# EEZ_CF-DIC_r3B2.net
KiCad netlist of a schematic drawn in EAGLE
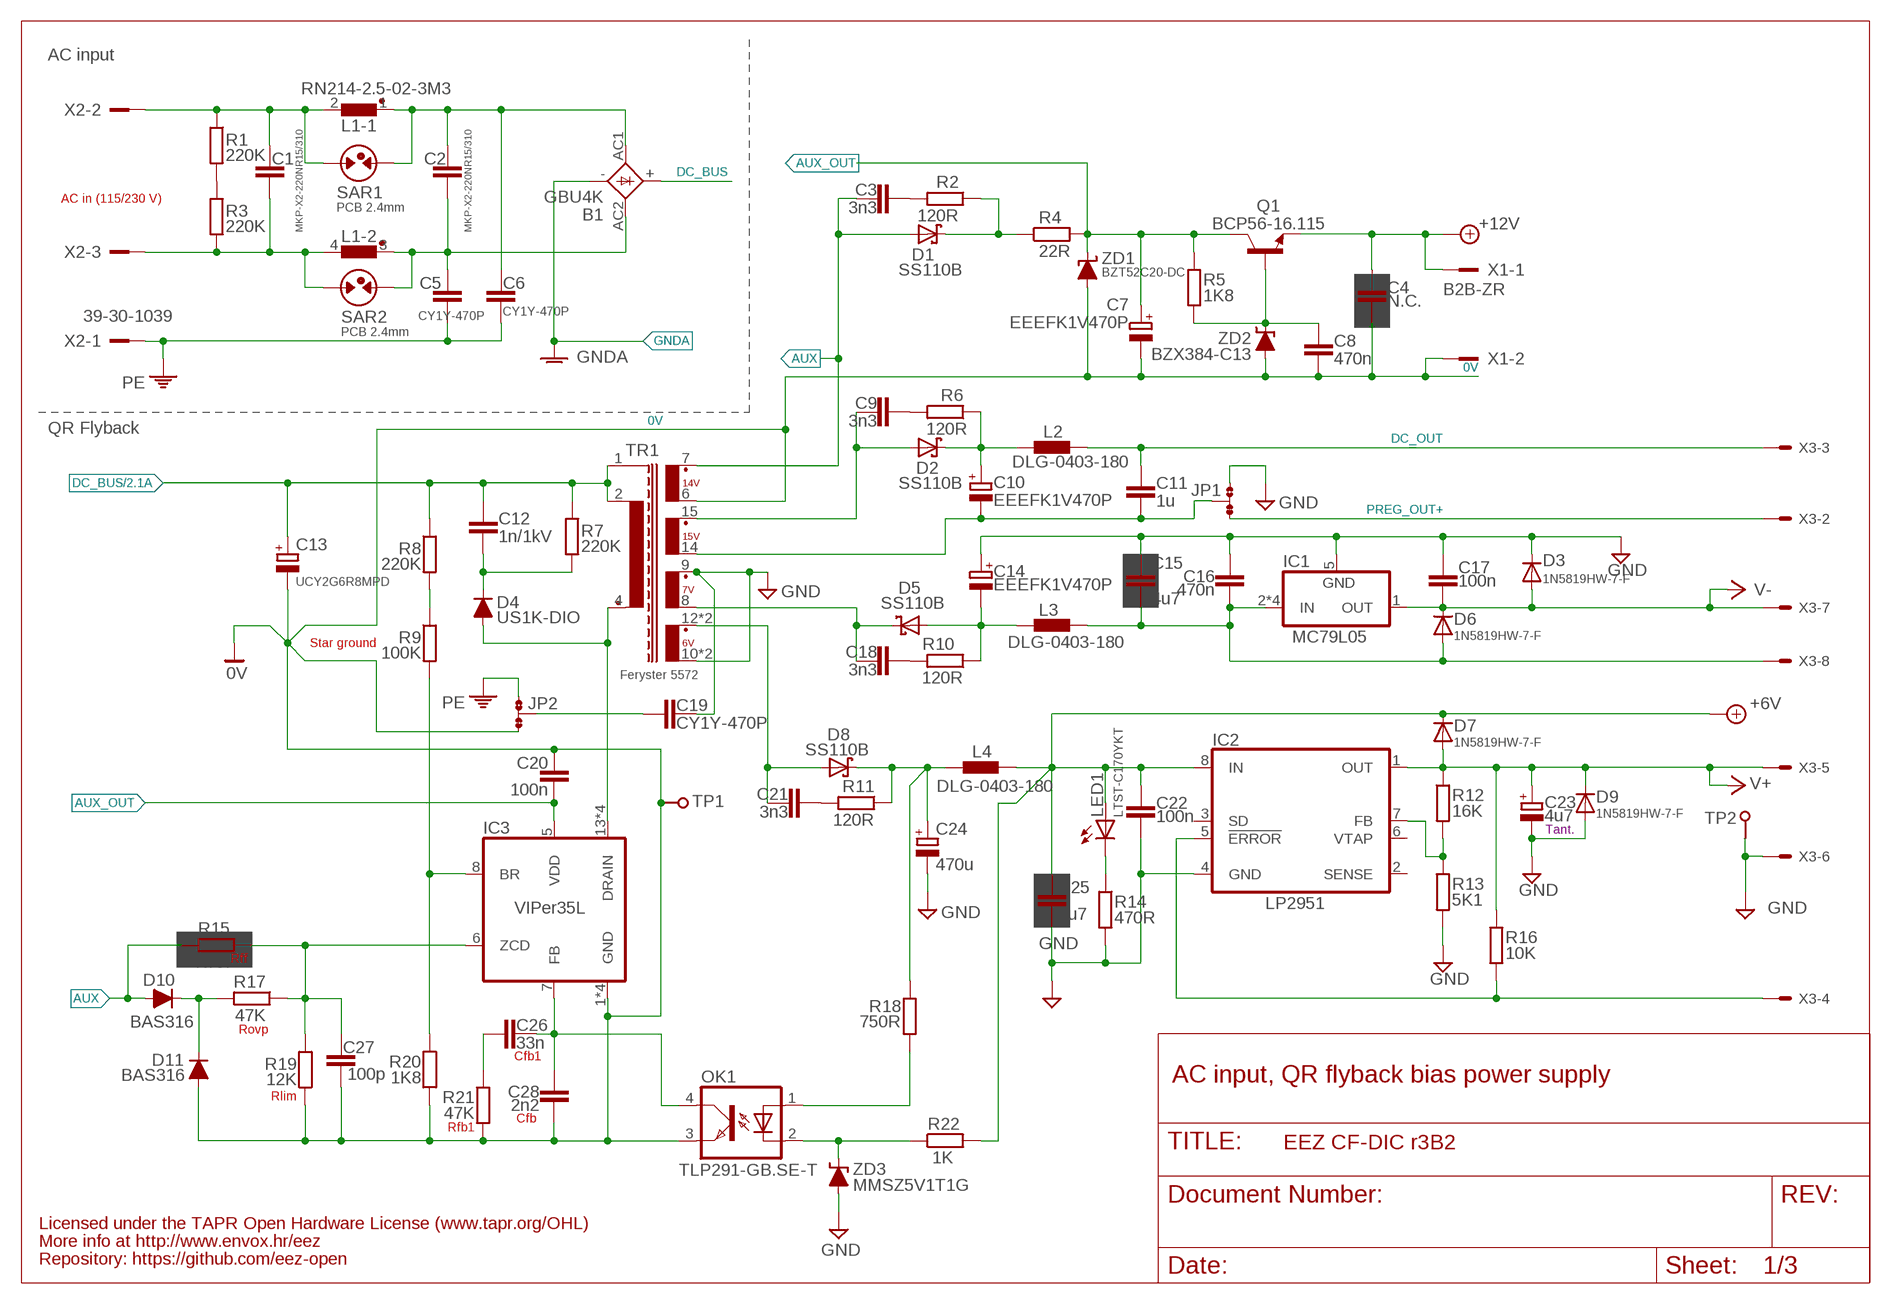
[diagram p0: schematic, sheet 1]
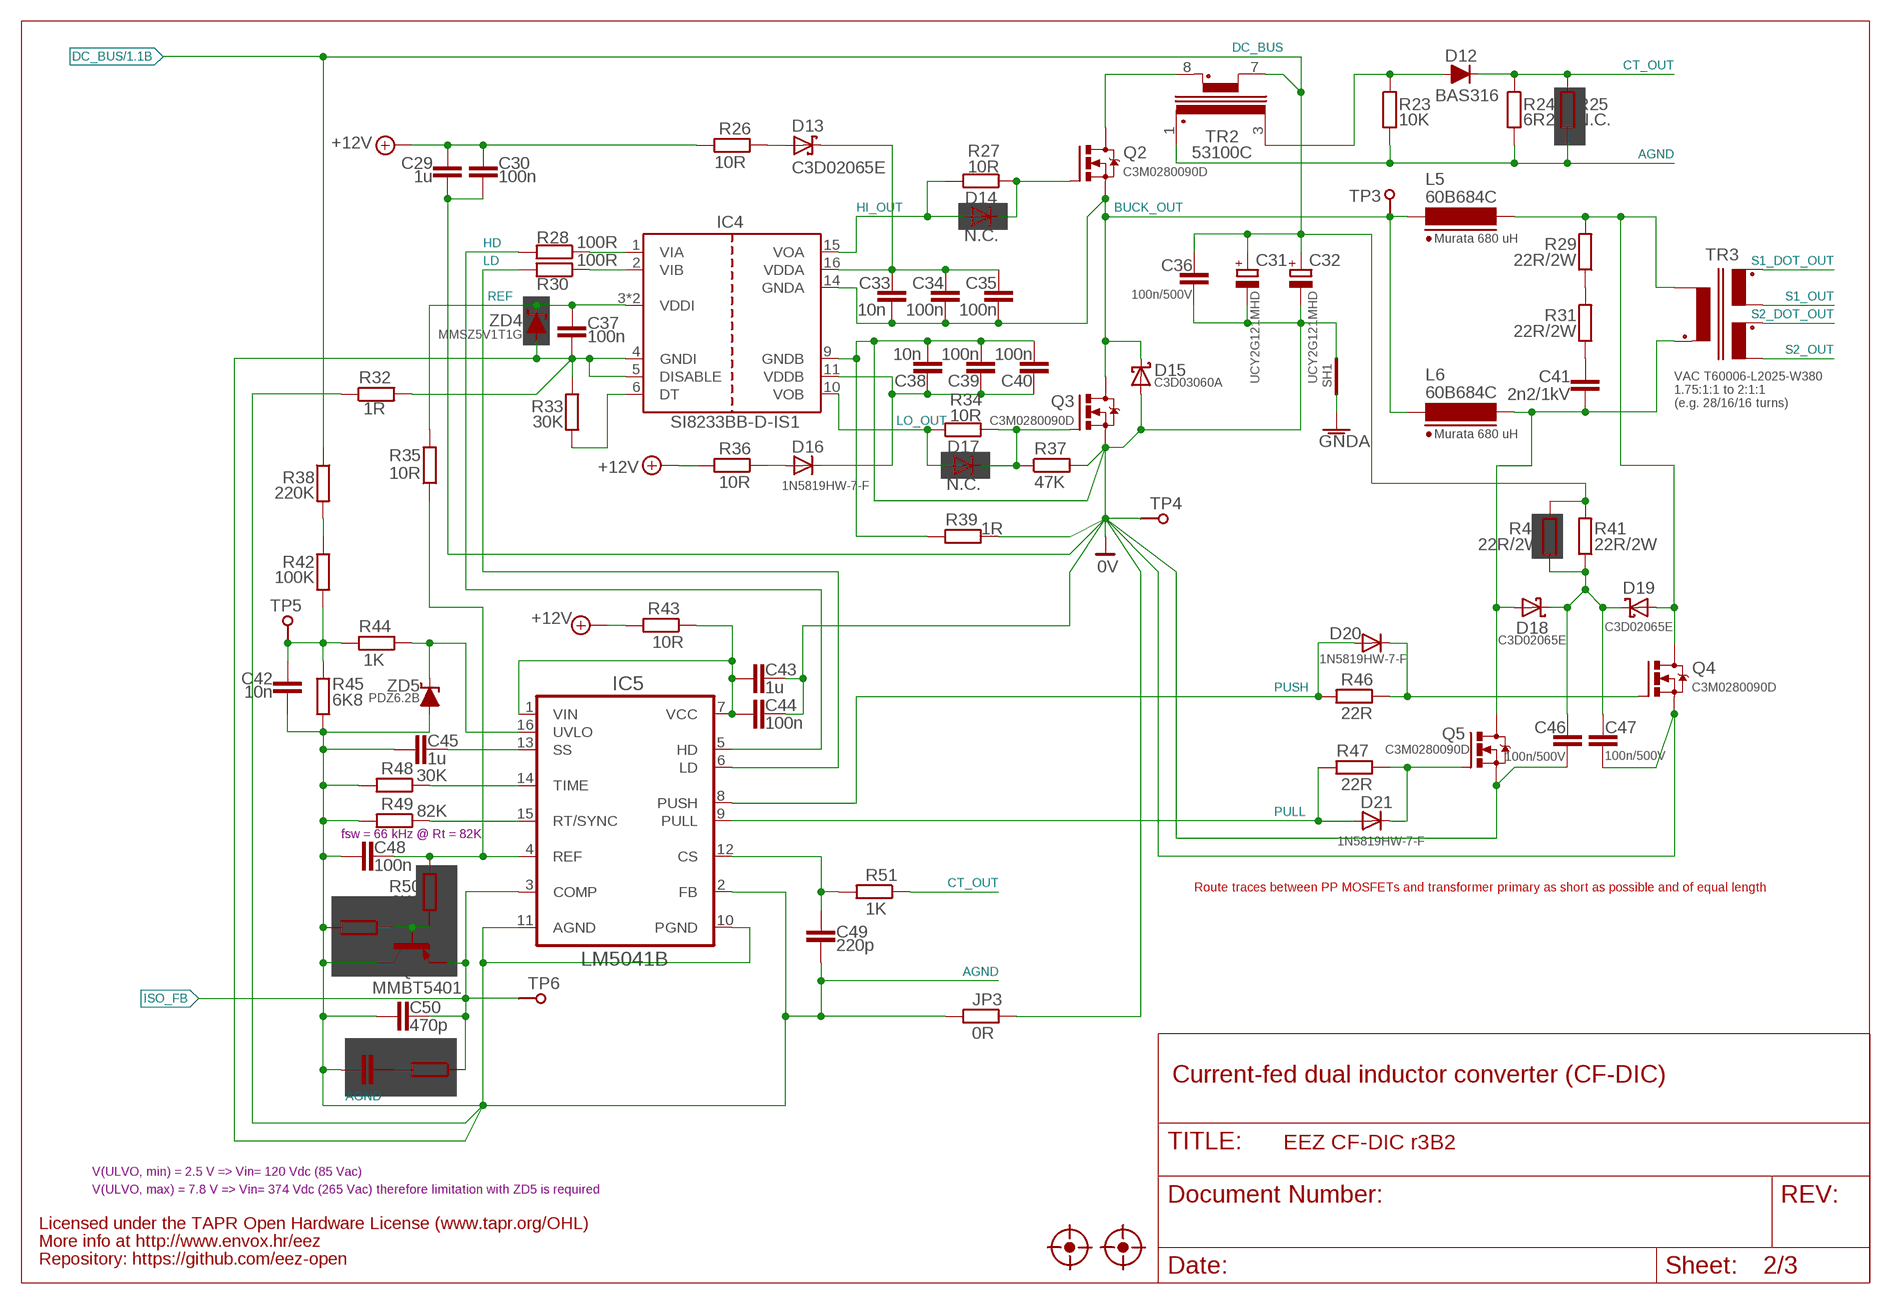
[diagram p1: schematic, sheet 2]
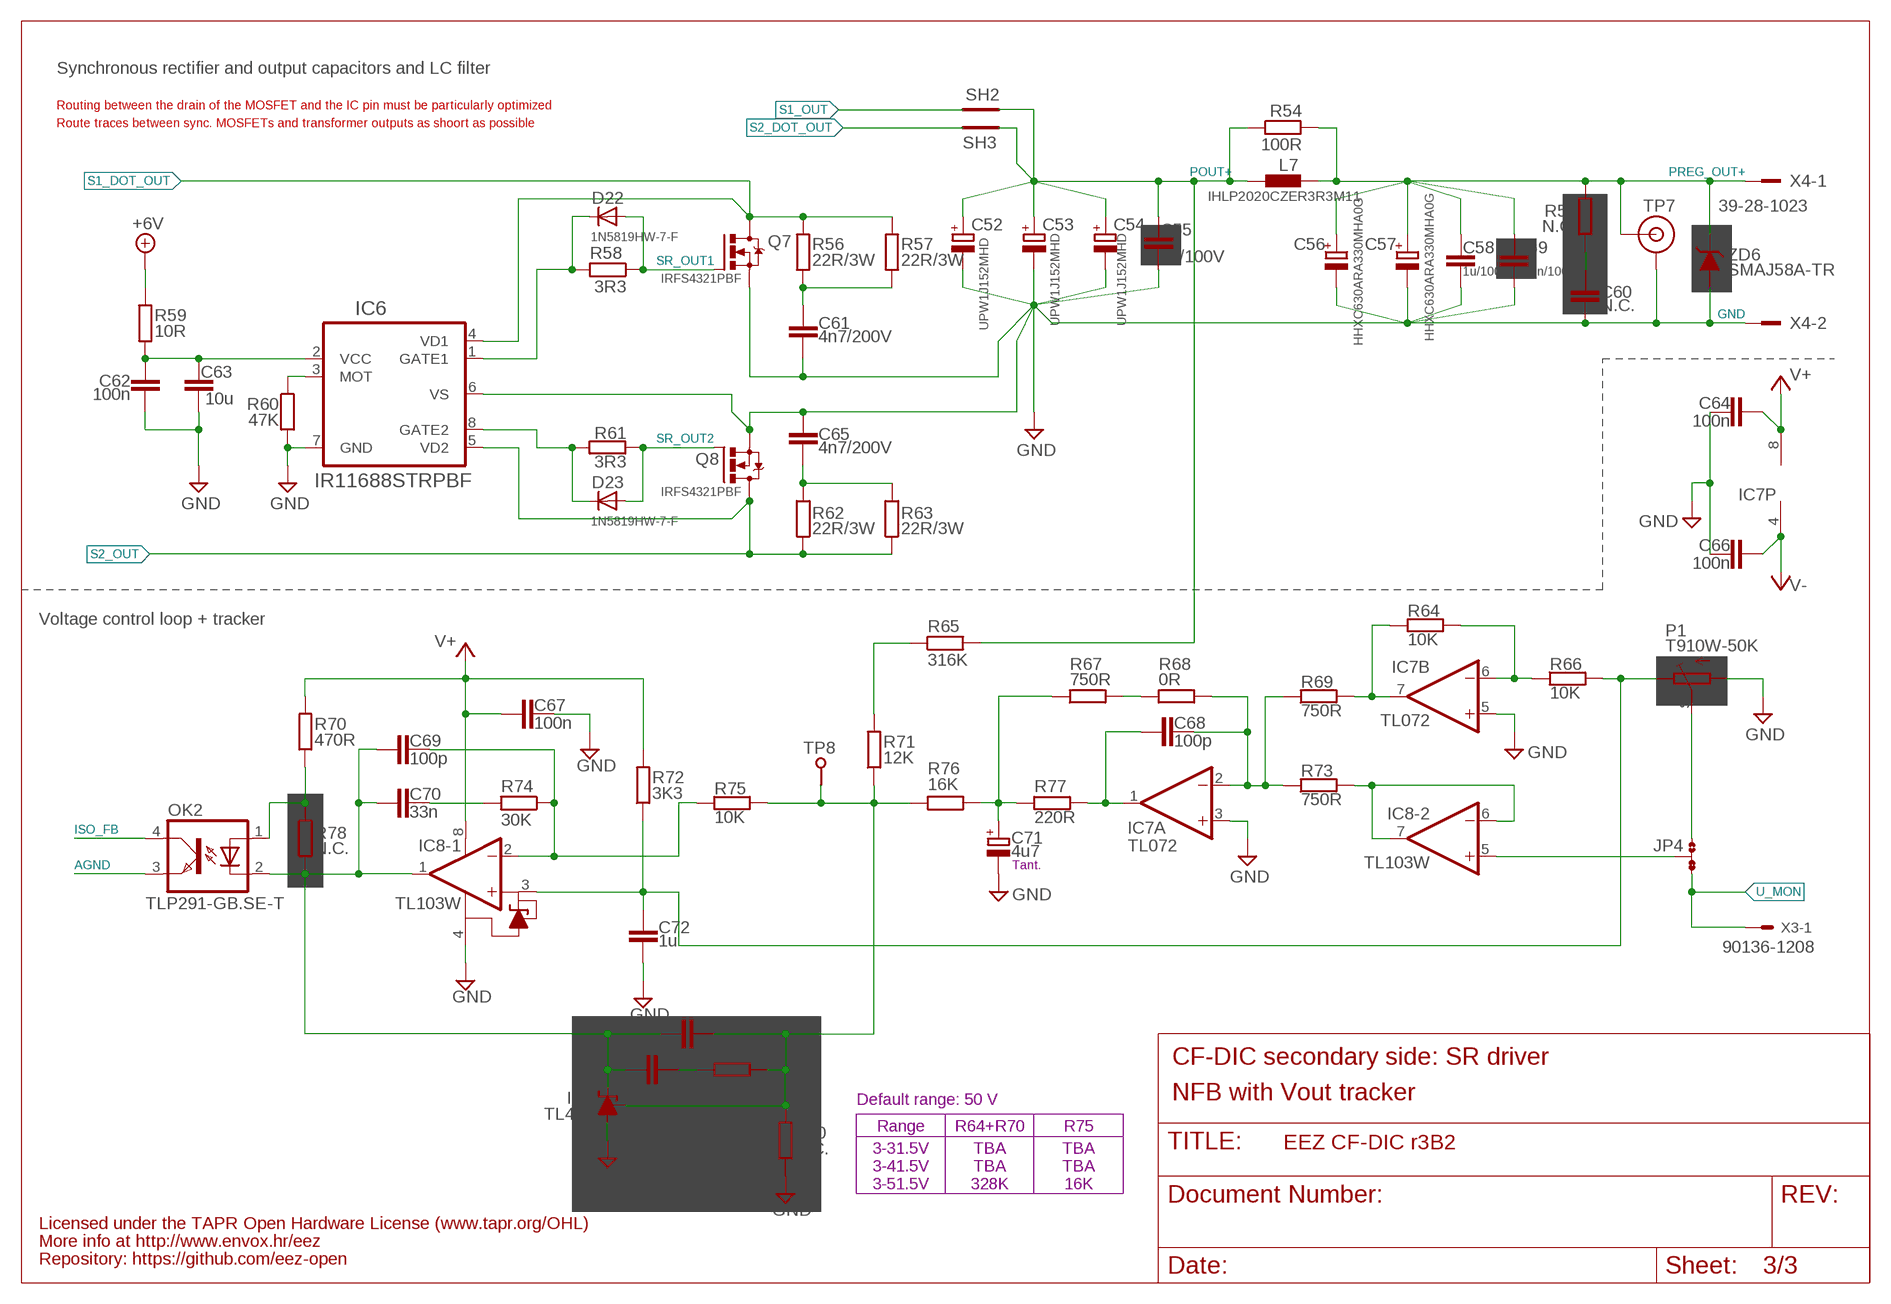
[diagram p2: schematic, sheet 3]

(export (version "E")
  (design (tool "Eeschema 10.0.6"))
  (components
    (comp (ref "C52")
      (value "UPW1J152MHD")
      (footprint "eagle-import:ECAP7.5_18")
      (libsource (lib "eagle-import") (part "ECAP7.5G_18MM"))
    )
    (comp (ref "C53")
      (value "UPW1J152MHD")
      (footprint "eagle-import:ECAP7.5_18")
      (libsource (lib "eagle-import") (part "ECAP7.5G_18MM"))
    )
    (comp (ref "C54")
      (value "UPW1J152MHD")
      (footprint "eagle-import:ECAP7.5_18")
      (libsource (lib "eagle-import") (part "ECAP7.5G_18MM"))
    )
    (comp (ref "C55")
      (value "1u/100V")
      (footprint "eagle-import:C1206")
      (libsource (lib "eagle-import") (part "C-EUC1206"))
    )
    (comp (ref "C56")
      (value "HHXC630ARA330MHA0G ")
      (footprint "eagle-import:CAPAE830X1050N")
      (fields
        (field (name "MPN") "EEE-FK1J470P")
        (field (name "TOLERANCE") "±20 %")
        (field (name "MPN_1") "EEE-FK1J470P")
        (field (name "OC_FARNELL") "9696032  ")
        (field (name "OC_NEWARK") "96K9403")
        (field (name "PACKAGE") "CASE-F")
        (field (name "SUPPLIER") "PANASONIC")
        (field (name "TOLERANCE_1") "±20 %")
        (field (name "VOLTAGERATING") "63 V")
      )
      (libsource (lib "eagle-import") (part "EEE--CASE-FFK1J470P"))
    )
    (comp (ref "C57")
      (value "HHXC630ARA330MHA0G")
      (footprint "eagle-import:CAPAE830X1050N")
      (fields (field (name "MPN") "EEE-FK1J470P") (field (name "TOLERANCE") "±20 %"))
      (libsource (lib "eagle-import") (part "EEE--CASE-FFK1J470P"))
    )
    (comp (ref "C58")
      (value "1u/100V")
      (footprint "eagle-import:C1206")
      (libsource (lib "eagle-import") (part "C-EUC1206"))
    )
    (comp (ref "C59")
      (value "100n/100V")
      (footprint "eagle-import:C0805")
      (libsource (lib "eagle-import") (part "C-EUC0805"))
    )
    (comp (ref "C60")
      (value "N.C.")
      (footprint "eagle-import:C1206")
      (libsource (lib "eagle-import") (part "C-EUC1206"))
    )
    (comp (ref "C61")
      (value "4n7/200V")
      (footprint "eagle-import:C1206")
      (libsource (lib "eagle-import") (part "C-EUC1206"))
    )
    (comp (ref "C62")
      (value "100n")
      (footprint "eagle-import:C0603")
      (libsource (lib "eagle-import") (part "C-EUC0603"))
    )
    (comp (ref "C63")
      (value "10u")
      (footprint "eagle-import:C1210")
      (libsource (lib "eagle-import") (part "C-EUC1210"))
    )
    (comp (ref "C64")
      (value "100n")
      (footprint "eagle-import:C0603")
      (libsource (lib "eagle-import") (part "C-EUC0603"))
    )
    (comp (ref "C65")
      (value "4n7/200V")
      (footprint "eagle-import:C1206")
      (libsource (lib "eagle-import") (part "C-EUC1206"))
    )
    (comp (ref "C66")
      (value "100n")
      (footprint "eagle-import:C0603")
      (libsource (lib "eagle-import") (part "C-EUC0603"))
    )
    (comp (ref "C67")
      (value "100n")
      (footprint "eagle-import:C0603")
      (libsource (lib "eagle-import") (part "C-EUC0603"))
    )
    (comp (ref "C68")
      (value "100p")
      (footprint "eagle-import:C0805")
      (libsource (lib "eagle-import") (part "C-EUC0805"))
    )
    (comp (ref "C69")
      (value "100p")
      (footprint "eagle-import:C0805")
      (libsource (lib "eagle-import") (part "C-EUC0805"))
    )
    (comp (ref "C70")
      (value "33n")
      (footprint "eagle-import:C0805")
      (libsource (lib "eagle-import") (part "C-EUC0805"))
    )
    (comp (ref "C71")
      (value "4u7")
      (footprint "eagle-import:EC1206")
      (libsource (lib "eagle-import") (part "ECAP1206"))
    )
    (comp (ref "C72")
      (value "1u")
      (footprint "eagle-import:C0805")
      (libsource (lib "eagle-import") (part "C-EUC0805"))
    )
    (comp (ref "C73")
      (value "N.C.")
      (footprint "eagle-import:C0805")
      (libsource (lib "eagle-import") (part "C-EUC0805"))
    )
    (comp (ref "C74")
      (value "N.C.")
      (footprint "eagle-import:C0805")
      (libsource (lib "eagle-import") (part "C-EUC0805"))
    )
    (comp (ref "D22")
      (value "1N5819HW-7-F")
      (footprint "eagle-import:SOD323-W")
      (libsource (lib "eagle-import") (part "DIODE-SOD323-W"))
    )
    (comp (ref "D23")
      (value "1N5819HW-7-F")
      (footprint "eagle-import:SOD323-W")
      (libsource (lib "eagle-import") (part "DIODE-SOD323-W"))
    )
    (comp (ref "IC6")
      (value "IR11688STRPBF")
      (footprint "eagle-import:SO8")
      (libsource (lib "eagle-import") (part "IR11688"))
    )
    (comp (ref "IC7")
      (value "TL072")
      (footprint "eagle-import:SOIC127P600X173-8N")
      (libsource (lib "eagle-import") (part "TL072SOIC8"))
    )
    (comp (ref "IC8")
      (value "TL103W")
      (footprint "eagle-import:SOIC127P600X173-8N")
      (libsource (lib "eagle-import") (part "TL103W"))
    )
    (comp (ref "IC9")
      (value "TL431")
      (footprint "eagle-import:SOT103P240X110-3N")
      (libsource (lib "eagle-import") (part "TL431"))
    )
    (comp (ref "JP4")
      (value "JP3-CUT")
      (footprint "eagle-import:JP3-CUT")
      (libsource (lib "eagle-import") (part "JP3-CUT"))
    )
    (comp (ref "L7")
      (value "IHLP2020CZER3R3M11")
      (footprint "eagle-import:IHLP-2020BZ-11")
      (libsource (lib "eagle-import") (part "EEZ_inductors_and_transformers_IHLP-2020BZ-11"))
    )
    (comp (ref "OK2")
      (value "TLP291-GB.SE-T")
      (footprint "eagle-import:SO4")
      (libsource (lib "eagle-import") (part "TLP291"))
    )
    (comp (ref "P1")
      (value "T910W-50K")
      (footprint "eagle-import:S64W")
      (libsource (lib "eagle-import") (part "TRIM_EU-S64W"))
    )
    (comp (ref "Q7")
      (value "IRFS4321PBF")
      (footprint "eagle-import:TO263")
      (libsource (lib "eagle-import") (part "N-MOSFETTO263"))
    )
    (comp (ref "Q8")
      (value "IRFS4321PBF")
      (footprint "eagle-import:TO263")
      (libsource (lib "eagle-import") (part "N-MOSFETTO263"))
    )
    (comp (ref "R54")
      (value "100R")
      (footprint "eagle-import:R0805")
      (libsource (lib "eagle-import") (part "R-EU_R0805"))
    )
    (comp (ref "R55")
      (value "N.C.")
      (footprint "eagle-import:R1210")
      (libsource (lib "eagle-import") (part "R-EU_R1210"))
    )
    (comp (ref "R56")
      (value "22R/3W")
      (footprint "eagle-import:R2512")
      (libsource (lib "eagle-import") (part "R-EU_R2512"))
    )
    (comp (ref "R57")
      (value "22R/3W")
      (footprint "eagle-import:R2512")
      (libsource (lib "eagle-import") (part "R-EU_R2512"))
    )
    (comp (ref "R58")
      (value "3R3")
      (footprint "eagle-import:R0805")
      (libsource (lib "eagle-import") (part "R-EU_R0805"))
    )
    (comp (ref "R59")
      (value "10R")
      (footprint "eagle-import:R0805")
      (libsource (lib "eagle-import") (part "R-EU_R0805"))
    )
    (comp (ref "R60")
      (value "47K")
      (footprint "eagle-import:R0805")
      (libsource (lib "eagle-import") (part "R-EU_R0805"))
    )
    (comp (ref "R61")
      (value "3R3")
      (footprint "eagle-import:R0805")
      (libsource (lib "eagle-import") (part "R-EU_R0805"))
    )
    (comp (ref "R62")
      (value "22R/3W")
      (footprint "eagle-import:R2512")
      (libsource (lib "eagle-import") (part "R-EU_R2512"))
    )
    (comp (ref "R63")
      (value "22R/3W")
      (footprint "eagle-import:R2512")
      (libsource (lib "eagle-import") (part "R-EU_R2512"))
    )
    (comp (ref "R64")
      (value "10K")
      (footprint "eagle-import:R0805")
      (libsource (lib "eagle-import") (part "R-EU_R0805"))
    )
    (comp (ref "R65")
      (value "316K")
      (footprint "eagle-import:R0805")
      (libsource (lib "eagle-import") (part "R-EU_R0805"))
    )
    (comp (ref "R66")
      (value "10K")
      (footprint "eagle-import:R0805")
      (libsource (lib "eagle-import") (part "R-EU_R0805"))
    )
    (comp (ref "R67")
      (value "750R")
      (footprint "eagle-import:R0805")
      (libsource (lib "eagle-import") (part "R-EU_R0805"))
    )
    (comp (ref "R68")
      (value "0R")
      (footprint "eagle-import:R0805")
      (libsource (lib "eagle-import") (part "R-EU_R0805"))
    )
    (comp (ref "R69")
      (value "750R")
      (footprint "eagle-import:R0805")
      (libsource (lib "eagle-import") (part "R-EU_R0805"))
    )
    (comp (ref "R70")
      (value "470R")
      (footprint "eagle-import:R0805")
      (libsource (lib "eagle-import") (part "R-EU_R0805"))
    )
    (comp (ref "R71")
      (value "12K")
      (footprint "eagle-import:R0805")
      (libsource (lib "eagle-import") (part "R-EU_R0805"))
    )
    (comp (ref "R72")
      (value "3K3")
      (footprint "eagle-import:R0805")
      (libsource (lib "eagle-import") (part "R-EU_R0805"))
    )
    (comp (ref "R73")
      (value "750R")
      (footprint "eagle-import:R0805")
      (libsource (lib "eagle-import") (part "R-EU_R0805"))
    )
    (comp (ref "R74")
      (value "30K")
      (footprint "eagle-import:R0805")
      (libsource (lib "eagle-import") (part "R-EU_R0805"))
    )
    (comp (ref "R75")
      (value "10K")
      (footprint "eagle-import:R0805")
      (libsource (lib "eagle-import") (part "R-EU_R0805"))
    )
    (comp (ref "R76")
      (value "16K")
      (footprint "eagle-import:R0805")
      (libsource (lib "eagle-import") (part "R-EU_R0805"))
    )
    (comp (ref "R77")
      (value "220R")
      (footprint "eagle-import:R0805")
      (libsource (lib "eagle-import") (part "R-EU_R0805"))
    )
    (comp (ref "R78")
      (value "N.C.")
      (footprint "eagle-import:R0805")
      (libsource (lib "eagle-import") (part "R-EU_R0805"))
    )
    (comp (ref "R79")
      (value "N.C.")
      (footprint "eagle-import:R0805")
      (libsource (lib "eagle-import") (part "R-EU_R0805"))
    )
    (comp (ref "R80")
      (value "N.C.")
      (footprint "eagle-import:R0805")
      (libsource (lib "eagle-import") (part "R-EU_R0805"))
    )
    (comp (ref "SH2")
      (value "SHORTNOHOLE")
      (footprint "eagle-import:SHORT_NOHOLE")
      (libsource (lib "eagle-import") (part "SHORTNOHOLE"))
    )
    (comp (ref "SH3")
      (value "SHORTNOHOLE")
      (footprint "eagle-import:SHORT_NOHOLE")
      (libsource (lib "eagle-import") (part "SHORTNOHOLE"))
    )
    (comp (ref "TP7")
      (value "TEST_POINT-2")
      (footprint "eagle-import:TP_1.1MM_2")
      (libsource (lib "eagle-import") (part "TEST_POINT-2"))
    )
    (comp (ref "TP8")
      (value "PCB_TEST_TABSHIELD")
      (footprint "eagle-import:PCB_SHIELD_TAB")
      (libsource (lib "eagle-import") (part "PCB_TEST_TABSHIELD"))
    )
    (comp (ref "X3")
      (value "90136-1208")
      (footprint "eagle-import:70543-08")
      (libsource (lib "eagle-import") (part "C-GRID-08-70543"))
    )
    (comp (ref "X4")
      (value "39-28-1023")
      (footprint "eagle-import:MINIFIT_5566-02A")
      (libsource (lib "eagle-import") (part "MINIFIT_5566-02A"))
    )
    (comp (ref "ZD6")
      (value "SMAJ58A-TR")
      (footprint "eagle-import:DO214AC")
      (libsource (lib "eagle-import") (part "PSMAXX"))
    )
    (comp (ref "B1")
      (value "GBU4K")
      (footprint "eagle-import:GBU4K_CRE")
      (libsource (lib "eagle-import") (part "BRIDGE-CREEPAGE"))
    )
    (comp (ref "C1")
      (value "MKP-X2-220NR15/310")
      (footprint "eagle-import:C150-084X183")
      (libsource (lib "eagle-import") (part "C-EU150-084X183"))
    )
    (comp (ref "C2")
      (value "MKP-X2-220NR15/310")
      (footprint "eagle-import:C150-084X183")
      (libsource (lib "eagle-import") (part "C-EU150-084X183"))
    )
    (comp (ref "C3")
      (value "3n3")
      (footprint "eagle-import:C0805")
      (libsource (lib "eagle-import") (part "C-EUC0805"))
    )
    (comp (ref "C4")
      (value "N.C.")
      (footprint "eagle-import:C0603")
      (libsource (lib "eagle-import") (part "C-EUC0603"))
    )
    (comp (ref "C5")
      (value "CY1Y-470P")
      (footprint "eagle-import:CY075-032X103")
      (libsource (lib "eagle-import") (part "C-EUCY"))
    )
    (comp (ref "C6")
      (value "CY1Y-470P")
      (footprint "eagle-import:CY075-032X103")
      (libsource (lib "eagle-import") (part "C-EUCY"))
    )
    (comp (ref "C7")
      (value "EEEFK1V470P")
      (footprint "eagle-import:CAPAE660X610N")
      (libsource (lib "eagle-import") (part "ECAPPANASONIC_H"))
    )
    (comp (ref "C8")
      (value "470n")
      (footprint "eagle-import:C0805")
      (libsource (lib "eagle-import") (part "C-EUC0805"))
    )
    (comp (ref "C9")
      (value "3n3")
      (footprint "eagle-import:C0805")
      (libsource (lib "eagle-import") (part "C-EUC0805"))
    )
    (comp (ref "C10")
      (value "EEEFK1V470P")
      (footprint "eagle-import:CAPAE660X610N")
      (libsource (lib "eagle-import") (part "ECAPPANASONIC_H"))
    )
    (comp (ref "C11")
      (value "1u")
      (footprint "eagle-import:C0805")
      (libsource (lib "eagle-import") (part "C-EUC0805"))
    )
    (comp (ref "C12")
      (value "1n/1kV")
      (footprint "eagle-import:C1210")
      (libsource (lib "eagle-import") (part "C-EUC1210"))
    )
    (comp (ref "C13")
      (value "UCY2G6R8MPD")
      (footprint "eagle-import:ECAP5_10.5")
      (libsource (lib "eagle-import") (part "ECAP5G_10.5MM"))
    )
    (comp (ref "C14")
      (value "EEEFK1V470P")
      (footprint "eagle-import:CAPAE660X610N")
      (libsource (lib "eagle-import") (part "ECAPPANASONIC_H"))
    )
    (comp (ref "C15")
      (value "4u7")
      (footprint "eagle-import:C1206")
      (libsource (lib "eagle-import") (part "C-EUC1206"))
    )
    (comp (ref "C16")
      (value "470n")
      (footprint "eagle-import:C0805")
      (libsource (lib "eagle-import") (part "C-EUC0805"))
    )
    (comp (ref "C17")
      (value "100n")
      (footprint "eagle-import:C0603")
      (libsource (lib "eagle-import") (part "C-EUC0603"))
    )
    (comp (ref "C18")
      (value "3n3")
      (footprint "eagle-import:C0805")
      (libsource (lib "eagle-import") (part "C-EUC0805"))
    )
    (comp (ref "C19")
      (value "CY1Y-470P")
      (footprint "eagle-import:CY075-032X103")
      (libsource (lib "eagle-import") (part "C-EUCY"))
    )
    (comp (ref "C20")
      (value "100n")
      (footprint "eagle-import:C0603")
      (libsource (lib "eagle-import") (part "C-EUC0603"))
    )
    (comp (ref "C21")
      (value "3n3")
      (footprint "eagle-import:C0805")
      (libsource (lib "eagle-import") (part "C-EUC0805"))
    )
    (comp (ref "C22")
      (value "100n")
      (footprint "eagle-import:C0603")
      (libsource (lib "eagle-import") (part "C-EUC0603"))
    )
    (comp (ref "C23")
      (value "4u7")
      (footprint "eagle-import:EC1206")
      (libsource (lib "eagle-import") (part "ECAP1206"))
    )
    (comp (ref "C24")
      (value "470u")
      (footprint "eagle-import:ECAP5_10.5")
      (libsource (lib "eagle-import") (part "ECAP5G_10.5MM"))
    )
    (comp (ref "C25")
      (value "4u7")
      (footprint "eagle-import:C1206")
      (libsource (lib "eagle-import") (part "C-EUC1206"))
    )
    (comp (ref "C26")
      (value "33n")
      (footprint "eagle-import:C0805")
      (libsource (lib "eagle-import") (part "C-EUC0805"))
    )
    (comp (ref "C27")
      (value "100p")
      (footprint "eagle-import:C0805")
      (libsource (lib "eagle-import") (part "C-EUC0805"))
    )
    (comp (ref "C28")
      (value "2n2")
      (footprint "eagle-import:C0805")
      (libsource (lib "eagle-import") (part "C-EUC0805"))
    )
    (comp (ref "D1")
      (value "SS110B")
      (footprint "eagle-import:SMB")
      (libsource (lib "eagle-import") (part "SCHOTTKYSMB"))
    )
    (comp (ref "D2")
      (value "SS110B")
      (footprint "eagle-import:SMB")
      (libsource (lib "eagle-import") (part "SCHOTTKYSMB"))
    )
    (comp (ref "D3")
      (value "1N5819HW-7-F")
      (footprint "eagle-import:SOD323-W")
      (libsource (lib "eagle-import") (part "DIODE-SOD323-W"))
    )
    (comp (ref "D4")
      (value "US1K-DIO")
      (footprint "eagle-import:DO214AA")
      (libsource (lib "eagle-import") (part "DIODEDO214AA"))
    )
    (comp (ref "D5")
      (value "SS110B")
      (footprint "eagle-import:SMB")
      (libsource (lib "eagle-import") (part "SCHOTTKYSMB"))
    )
    (comp (ref "D6")
      (value "1N5819HW-7-F")
      (footprint "eagle-import:SOD323-W")
      (libsource (lib "eagle-import") (part "DIODE-SOD323-W"))
    )
    (comp (ref "D7")
      (value "1N5819HW-7-F")
      (footprint "eagle-import:SOD323-W")
      (libsource (lib "eagle-import") (part "DIODE-SOD323-W"))
    )
    (comp (ref "D8")
      (value "SS110B")
      (footprint "eagle-import:SMB")
      (libsource (lib "eagle-import") (part "SCHOTTKYSMB"))
    )
    (comp (ref "D9")
      (value "1N5819HW-7-F")
      (footprint "eagle-import:SOD323-W")
      (libsource (lib "eagle-import") (part "DIODE-SOD323-W"))
    )
    (comp (ref "D10")
      (value "BAS316")
      (footprint "eagle-import:SOD323-R")
      (libsource (lib "eagle-import") (part "DIODESOD323R"))
    )
    (comp (ref "D11")
      (value "BAS316")
      (footprint "eagle-import:SOD323-R")
      (libsource (lib "eagle-import") (part "DIODESOD323R"))
    )
    (comp (ref "IC1")
      (value "MC79L05")
      (footprint "eagle-import:SOIC127P600X173-8N")
      (libsource (lib "eagle-import") (part "MC79LXXSOIC"))
    )
    (comp (ref "IC2")
      (value "LP2951")
      (footprint "eagle-import:SOIC127P600X175-8N")
      (libsource (lib "eagle-import") (part "LP2951SO8"))
    )
    (comp (ref "IC3")
      (value "VIPer35L")
      (footprint "eagle-import:SOIC-16")
      (libsource (lib "eagle-import") (part "VIPER35"))
    )
    (comp (ref "JP1")
      (value "JP3-CUT")
      (footprint "eagle-import:JP3-CUT")
      (libsource (lib "eagle-import") (part "JP3-CUT"))
    )
    (comp (ref "JP2")
      (value "JP3-CUT")
      (footprint "eagle-import:JP3-CUT")
      (libsource (lib "eagle-import") (part "JP3-CUT"))
    )
    (comp (ref "L1")
      (value "RN214-2.5-02-3M3")
      (footprint "eagle-import:RN214")
      (fields (field (name "FARNELL") "1191518"))
      (libsource (lib "eagle-import") (part "EEZ_inductors_and_transformers_RN214"))
    )
    (comp (ref "L2")
      (value "DLG-0403-180")
      (footprint "eagle-import:DE0403")
      (libsource (lib "eagle-import") (part "EEZ_inductors_and_transformers_DE0403"))
    )
    (comp (ref "L3")
      (value "DLG-0403-180")
      (footprint "eagle-import:DE0403")
      (libsource (lib "eagle-import") (part "EEZ_inductors_and_transformers_DE0403"))
    )
    (comp (ref "L4")
      (value "DLG-0403-180")
      (footprint "eagle-import:DE0403")
      (libsource (lib "eagle-import") (part "EEZ_inductors_and_transformers_DE0403"))
    )
    (comp (ref "LED1")
      (value "LTST-C170YKT")
      (footprint "eagle-import:LED_0805")
      (libsource (lib "eagle-import") (part "LED0805"))
    )
    (comp (ref "OK1")
      (value "TLP291-GB.SE-T")
      (footprint "eagle-import:SO4")
      (libsource (lib "eagle-import") (part "TLP291"))
    )
    (comp (ref "Q1")
      (value "BCP56-16.115")
      (footprint "eagle-import:SOT230P700X180-4N")
      (libsource (lib "eagle-import") (part "BCP56"))
    )
    (comp (ref "R1")
      (value "220K")
      (footprint "eagle-import:R1206")
      (libsource (lib "eagle-import") (part "R-EU_R1206"))
    )
    (comp (ref "R2")
      (value "120R")
      (footprint "eagle-import:R0805")
      (libsource (lib "eagle-import") (part "R-EU_R0805"))
    )
    (comp (ref "R3")
      (value "220K")
      (footprint "eagle-import:R1206")
      (libsource (lib "eagle-import") (part "R-EU_R1206"))
    )
    (comp (ref "R4")
      (value "22R")
      (footprint "eagle-import:R0805")
      (libsource (lib "eagle-import") (part "R-EU_R0805"))
    )
    (comp (ref "R5")
      (value "1K8")
      (footprint "eagle-import:R0805")
      (libsource (lib "eagle-import") (part "R-EU_R0805"))
    )
    (comp (ref "R6")
      (value "120R")
      (footprint "eagle-import:R0805")
      (libsource (lib "eagle-import") (part "R-EU_R0805"))
    )
    (comp (ref "R7")
      (value "220K")
      (footprint "eagle-import:R1206")
      (libsource (lib "eagle-import") (part "R-EU_R1206"))
    )
    (comp (ref "R8")
      (value "220K")
      (footprint "eagle-import:R1206")
      (libsource (lib "eagle-import") (part "R-EU_R1206"))
    )
    (comp (ref "R9")
      (value "100K")
      (footprint "eagle-import:R0805")
      (libsource (lib "eagle-import") (part "R-EU_R0805"))
    )
    (comp (ref "R10")
      (value "120R")
      (footprint "eagle-import:R0805")
      (libsource (lib "eagle-import") (part "R-EU_R0805"))
    )
    (comp (ref "R11")
      (value "120R")
      (footprint "eagle-import:R0805")
      (libsource (lib "eagle-import") (part "R-EU_R0805"))
    )
    (comp (ref "R12")
      (value "16K")
      (footprint "eagle-import:R0805")
      (libsource (lib "eagle-import") (part "R-EU_R0805"))
    )
    (comp (ref "R13")
      (value "5K1")
      (footprint "eagle-import:R0805")
      (libsource (lib "eagle-import") (part "R-EU_R0805"))
    )
    (comp (ref "R14")
      (value "470R")
      (footprint "eagle-import:R0805")
      (libsource (lib "eagle-import") (part "R-EU_R0805"))
    )
    (comp (ref "R15")
      (value "N.C.")
      (footprint "eagle-import:R0805")
      (libsource (lib "eagle-import") (part "R-EU_R0805"))
    )
    (comp (ref "R16")
      (value "10K")
      (footprint "eagle-import:R0805")
      (libsource (lib "eagle-import") (part "R-EU_R0805"))
    )
    (comp (ref "R17")
      (value "47K")
      (footprint "eagle-import:R0805")
      (libsource (lib "eagle-import") (part "R-EU_R0805"))
    )
    (comp (ref "R18")
      (value "750R")
      (footprint "eagle-import:R0805")
      (libsource (lib "eagle-import") (part "R-EU_R0805"))
    )
    (comp (ref "R19")
      (value "12K")
      (footprint "eagle-import:R0805")
      (libsource (lib "eagle-import") (part "R-EU_R0805"))
    )
    (comp (ref "R20")
      (value "1K8")
      (footprint "eagle-import:R0805")
      (libsource (lib "eagle-import") (part "R-EU_R0805"))
    )
    (comp (ref "R21")
      (value "47K")
      (footprint "eagle-import:R0805")
      (libsource (lib "eagle-import") (part "R-EU_R0805"))
    )
    (comp (ref "R22")
      (value "1K")
      (footprint "eagle-import:R0805")
      (libsource (lib "eagle-import") (part "R-EU_R0805"))
    )
    (comp (ref "SAR1")
      (value "PCB 2.4mm")
      (footprint "eagle-import:PCB-SAR_2.4MM")
      (libsource (lib "eagle-import") (part "SARPCB-2.4MM"))
    )
    (comp (ref "SAR2")
      (value "PCB 2.4mm")
      (footprint "eagle-import:PCB-SAR_2.4MM")
      (libsource (lib "eagle-import") (part "SARPCB-2.4MM"))
    )
    (comp (ref "TP1")
      (value "PCB_TEST_TABSHIELD")
      (footprint "eagle-import:PCB_SHIELD_TAB")
      (libsource (lib "eagle-import") (part "PCB_TEST_TABSHIELD"))
    )
    (comp (ref "TP2")
      (value "PCB_TEST_TABSHIELD")
      (footprint "eagle-import:PCB_SHIELD_TAB")
      (libsource (lib "eagle-import") (part "PCB_TEST_TABSHIELD"))
    )
    (comp (ref "TR1")
      (value "Feryster 5572")
      (footprint "eagle-import:FERYSTER_5572")
      (libsource (lib "eagle-import") (part "EEZ_inductors_and_transformers_FERYSTER_5572"))
    )
    (comp (ref "X1")
      (value "B2B-ZR")
      (footprint "eagle-import:B2B-ZR")
      (libsource (lib "eagle-import") (part "B2B-ZR"))
    )
    (comp (ref "X2")
      (value "39-30-1039")
      (footprint "eagle-import:MINIFIT_39301039_CRE")
      (libsource (lib "eagle-import") (part "MINIFIT_39301039-CREEPAGE"))
    )
    (comp (ref "ZD1")
      (value "BZT52C20-DC")
      (footprint "eagle-import:SOD123FL")
      (libsource (lib "eagle-import") (part "ZENER-DIODESOD123FL"))
    )
    (comp (ref "ZD2")
      (value "BZX384-C13")
      (footprint "eagle-import:SOD323-W")
      (libsource (lib "eagle-import") (part "ZENER-DIODESOD323"))
    )
    (comp (ref "ZD3")
      (value "MMSZ5V1T1G")
      (footprint "eagle-import:SOD323-W")
      (libsource (lib "eagle-import") (part "ZENER-DIODESOD323"))
    )
    (comp (ref "C29")
      (value "1u")
      (footprint "eagle-import:C0805")
      (libsource (lib "eagle-import") (part "C-EUC0805"))
    )
    (comp (ref "C30")
      (value "100n")
      (footprint "eagle-import:C0603")
      (libsource (lib "eagle-import") (part "C-EUC0603"))
    )
    (comp (ref "C31")
      (value "UCY2G121MHD")
      (footprint "eagle-import:ECAP7.5_18")
      (libsource (lib "eagle-import") (part "ECAP7.5G_18MM"))
    )
    (comp (ref "C32")
      (value "UCY2G121MHD")
      (footprint "eagle-import:ECAP7.5_18")
      (libsource (lib "eagle-import") (part "ECAP7.5G_18MM"))
    )
    (comp (ref "C33")
      (value "10n")
      (footprint "eagle-import:C0603")
      (libsource (lib "eagle-import") (part "C-EUC0603"))
    )
    (comp (ref "C34")
      (value "100n")
      (footprint "eagle-import:C0603")
      (libsource (lib "eagle-import") (part "C-EUC0603"))
    )
    (comp (ref "C35")
      (value "100n")
      (footprint "eagle-import:C0603")
      (libsource (lib "eagle-import") (part "C-EUC0603"))
    )
    (comp (ref "C36")
      (value "100n/500V")
      (footprint "eagle-import:C1812")
      (libsource (lib "eagle-import") (part "C-EUC1812"))
    )
    (comp (ref "C37")
      (value "100n")
      (footprint "eagle-import:C0603")
      (libsource (lib "eagle-import") (part "C-EUC0603"))
    )
    (comp (ref "C38")
      (value "10n")
      (footprint "eagle-import:C0603")
      (libsource (lib "eagle-import") (part "C-EUC0603"))
    )
    (comp (ref "C39")
      (value "100n")
      (footprint "eagle-import:C0603")
      (libsource (lib "eagle-import") (part "C-EUC0603"))
    )
    (comp (ref "C40")
      (value "100n")
      (footprint "eagle-import:C0603")
      (libsource (lib "eagle-import") (part "C-EUC0603"))
    )
    (comp (ref "C41")
      (value "2n2/1kV")
      (footprint "eagle-import:C1210")
      (libsource (lib "eagle-import") (part "C-EUC1210"))
    )
    (comp (ref "C42")
      (value "10n")
      (footprint "eagle-import:C0603")
      (libsource (lib "eagle-import") (part "C-EUC0603"))
    )
    (comp (ref "C43")
      (value "1u")
      (footprint "eagle-import:C0805")
      (libsource (lib "eagle-import") (part "C-EUC0805"))
    )
    (comp (ref "C44")
      (value "100n")
      (footprint "eagle-import:C0603")
      (libsource (lib "eagle-import") (part "C-EUC0603"))
    )
    (comp (ref "C45")
      (value "1u")
      (footprint "eagle-import:C0805")
      (libsource (lib "eagle-import") (part "C-EUC0805"))
    )
    (comp (ref "C46")
      (value "100n/500V")
      (footprint "eagle-import:C1812")
      (libsource (lib "eagle-import") (part "C-EUC1812"))
    )
    (comp (ref "C47")
      (value "100n/500V")
      (footprint "eagle-import:C1812")
      (libsource (lib "eagle-import") (part "C-EUC1812"))
    )
    (comp (ref "C48")
      (value "100n")
      (footprint "eagle-import:C0603")
      (libsource (lib "eagle-import") (part "C-EUC0603"))
    )
    (comp (ref "C49")
      (value "220p")
      (footprint "eagle-import:C0805")
      (libsource (lib "eagle-import") (part "C-EUC0805"))
    )
    (comp (ref "C50")
      (value "470p")
      (footprint "eagle-import:C0805")
      (libsource (lib "eagle-import") (part "C-EUC0805"))
    )
    (comp (ref "C51")
      (value "N.C.")
      (footprint "eagle-import:C0805")
      (libsource (lib "eagle-import") (part "C-EUC0805"))
    )
    (comp (ref "D12")
      (value "BAS316")
      (footprint "eagle-import:SOD323-R")
      (libsource (lib "eagle-import") (part "DIODESOD323R"))
    )
    (comp (ref "D13")
      (value "C3D02065E")
      (footprint "eagle-import:TO252")
      (libsource (lib "eagle-import") (part "SCHOTTKY-2"))
    )
    (comp (ref "D14")
      (value "N.C.")
      (footprint "eagle-import:SOD323-W")
      (libsource (lib "eagle-import") (part "DIODE-SOD323-W"))
    )
    (comp (ref "D15")
      (value "C3D03060A")
      (footprint "eagle-import:TO220-2")
      (libsource (lib "eagle-import") (part "SCHOTTKY-TO220"))
    )
    (comp (ref "D16")
      (value "1N5819HW-7-F")
      (footprint "eagle-import:SOD323-W")
      (libsource (lib "eagle-import") (part "DIODE-SOD323-W"))
    )
    (comp (ref "D17")
      (value "N.C.")
      (footprint "eagle-import:SOD323-W")
      (libsource (lib "eagle-import") (part "DIODE-SOD323-W"))
    )
    (comp (ref "D18")
      (value "C3D02065E")
      (footprint "eagle-import:TO252")
      (libsource (lib "eagle-import") (part "SCHOTTKY-2"))
    )
    (comp (ref "D19")
      (value "C3D02065E")
      (footprint "eagle-import:TO252")
      (libsource (lib "eagle-import") (part "SCHOTTKY-2"))
    )
    (comp (ref "D20")
      (value "1N5819HW-7-F")
      (footprint "eagle-import:SOD323-W")
      (libsource (lib "eagle-import") (part "DIODE-SOD323-W"))
    )
    (comp (ref "D21")
      (value "1N5819HW-7-F")
      (footprint "eagle-import:SOD323-W")
      (libsource (lib "eagle-import") (part "DIODE-SOD323-W"))
    )
    (comp (ref "FM1")
      (value "FIDUCIAL_2")
      (footprint "eagle-import:FIDUCIAL_DUAL")
      (libsource (lib "eagle-import") (part "FIDUCIAL_2"))
    )
    (comp (ref "FM2")
      (value "FIDUCIAL_2")
      (footprint "eagle-import:FIDUCIAL_DUAL")
      (libsource (lib "eagle-import") (part "FIDUCIAL_2"))
    )
    (comp (ref "IC4")
      (value "SI8233BB-D-IS1")
      (footprint "eagle-import:SOIC-16")
      (libsource (lib "eagle-import") (part "SI8233"))
    )
    (comp (ref "IC5")
      (value "LM5041B")
      (footprint "eagle-import:MTC16")
      (fields (field (name "MANUFACTURER_PART_NUMBER") "lm5041mtcnopb"))
      (libsource (lib "eagle-import") (part "LM5041"))
    )
    (comp (ref "JP3")
      (value "0R")
      (footprint "eagle-import:R0805")
      (libsource (lib "eagle-import") (part "R-EU_R0805"))
    )
    (comp (ref "L5")
      (value "60B684C")
      (footprint "eagle-import:MURATA_6000B")
      (libsource (lib "eagle-import") (part "EEZ_inductors_and_transformers_MURATA_6000B"))
    )
    (comp (ref "L6")
      (value "60B684C")
      (footprint "eagle-import:MURATA_6000B")
      (libsource (lib "eagle-import") (part "EEZ_inductors_and_transformers_MURATA_6000B"))
    )
    (comp (ref "Q2")
      (value "C3M0280090D")
      (footprint "eagle-import:TO247BV")
      (libsource (lib "eagle-import") (part "IRFP240"))
    )
    (comp (ref "Q3")
      (value "C3M0280090D")
      (footprint "eagle-import:TO247BV")
      (libsource (lib "eagle-import") (part "IRFP240"))
    )
    (comp (ref "Q4")
      (value "C3M0280090D")
      (footprint "eagle-import:TO247BV")
      (libsource (lib "eagle-import") (part "IRFP240"))
    )
    (comp (ref "Q5")
      (value "C3M0280090D")
      (footprint "eagle-import:TO247BV")
      (libsource (lib "eagle-import") (part "IRFP240"))
    )
    (comp (ref "Q6")
      (value "MMBT5401")
      (footprint "eagle-import:SOT23-BEC")
      (libsource (lib "eagle-import") (part "-PNP-SOT23-BECBC857B"))
    )
    (comp (ref "R23")
      (value "10K")
      (footprint "eagle-import:R0805")
      (libsource (lib "eagle-import") (part "R-EU_R0805"))
    )
    (comp (ref "R24")
      (value "6R2")
      (footprint "eagle-import:R0805")
      (libsource (lib "eagle-import") (part "R-EU_R0805"))
    )
    (comp (ref "R25")
      (value "N.C.")
      (footprint "eagle-import:R0805")
      (libsource (lib "eagle-import") (part "R-EU_R0805"))
    )
    (comp (ref "R26")
      (value "10R")
      (footprint "eagle-import:R0805")
      (libsource (lib "eagle-import") (part "R-EU_R0805"))
    )
    (comp (ref "R27")
      (value "10R")
      (footprint "eagle-import:R0805")
      (libsource (lib "eagle-import") (part "R-EU_R0805"))
    )
    (comp (ref "R28")
      (value "100R")
      (footprint "eagle-import:R0805")
      (libsource (lib "eagle-import") (part "R-EU_R0805"))
    )
    (comp (ref "R29")
      (value "22R/2W")
      (footprint "eagle-import:R2512")
      (libsource (lib "eagle-import") (part "R-EU_R2512"))
    )
    (comp (ref "R30")
      (value "100R")
      (footprint "eagle-import:R0805")
      (libsource (lib "eagle-import") (part "R-EU_R0805"))
    )
    (comp (ref "R31")
      (value "22R/2W")
      (footprint "eagle-import:R2512")
      (libsource (lib "eagle-import") (part "R-EU_R2512"))
    )
    (comp (ref "R32")
      (value "1R")
      (footprint "eagle-import:R0805")
      (libsource (lib "eagle-import") (part "R-EU_R0805"))
    )
    (comp (ref "R33")
      (value "30K")
      (footprint "eagle-import:R0805")
      (libsource (lib "eagle-import") (part "R-EU_R0805"))
    )
    (comp (ref "R34")
      (value "10R")
      (footprint "eagle-import:R0805")
      (libsource (lib "eagle-import") (part "R-EU_R0805"))
    )
    (comp (ref "R35")
      (value "10R")
      (footprint "eagle-import:R0805")
      (libsource (lib "eagle-import") (part "R-EU_R0805"))
    )
    (comp (ref "R36")
      (value "10R")
      (footprint "eagle-import:R0805")
      (libsource (lib "eagle-import") (part "R-EU_R0805"))
    )
    (comp (ref "R37")
      (value "47K")
      (footprint "eagle-import:R0805")
      (libsource (lib "eagle-import") (part "R-EU_R0805"))
    )
    (comp (ref "R38")
      (value "220K")
      (footprint "eagle-import:R1206")
      (libsource (lib "eagle-import") (part "R-EU_R1206"))
    )
    (comp (ref "R39")
      (value "1R")
      (footprint "eagle-import:R0805")
      (libsource (lib "eagle-import") (part "R-EU_R0805"))
    )
    (comp (ref "R40")
      (value "22R/2W")
      (footprint "eagle-import:R2512")
      (libsource (lib "eagle-import") (part "R-EU_R2512"))
    )
    (comp (ref "R41")
      (value "22R/2W")
      (footprint "eagle-import:R2512")
      (libsource (lib "eagle-import") (part "R-EU_R2512"))
    )
    (comp (ref "R42")
      (value "100K")
      (footprint "eagle-import:R0805")
      (libsource (lib "eagle-import") (part "R-EU_R0805"))
    )
    (comp (ref "R43")
      (value "10R")
      (footprint "eagle-import:R0805")
      (libsource (lib "eagle-import") (part "R-EU_R0805"))
    )
    (comp (ref "R44")
      (value "1K")
      (footprint "eagle-import:R0805")
      (libsource (lib "eagle-import") (part "R-EU_R0805"))
    )
    (comp (ref "R45")
      (value "6K8")
      (footprint "eagle-import:R0805")
      (libsource (lib "eagle-import") (part "R-EU_R0805"))
    )
    (comp (ref "R46")
      (value "22R")
      (footprint "eagle-import:R0805")
      (libsource (lib "eagle-import") (part "R-EU_R0805"))
    )
    (comp (ref "R47")
      (value "22R")
      (footprint "eagle-import:R0805")
      (libsource (lib "eagle-import") (part "R-EU_R0805"))
    )
    (comp (ref "R48")
      (value "30K")
      (footprint "eagle-import:R0805")
      (libsource (lib "eagle-import") (part "R-EU_R0805"))
    )
    (comp (ref "R49")
      (value "82K")
      (footprint "eagle-import:R0805")
      (libsource (lib "eagle-import") (part "R-EU_R0805"))
    )
    (comp (ref "R50")
      (value "6K8")
      (footprint "eagle-import:R0805")
      (libsource (lib "eagle-import") (part "R-EU_R0805"))
    )
    (comp (ref "R51")
      (value "1K")
      (footprint "eagle-import:R0805")
      (libsource (lib "eagle-import") (part "R-EU_R0805"))
    )
    (comp (ref "R52")
      (value "6K8")
      (footprint "eagle-import:R0805")
      (libsource (lib "eagle-import") (part "R-EU_R0805"))
    )
    (comp (ref "R53")
      (value "N.C.")
      (footprint "eagle-import:R0805")
      (libsource (lib "eagle-import") (part "R-EU_R0805"))
    )
    (comp (ref "SH1")
      (value "SHORTNOHOLE")
      (footprint "eagle-import:SHORT_NOHOLE")
      (libsource (lib "eagle-import") (part "SHORTNOHOLE"))
    )
    (comp (ref "TP3")
      (value "PCB_TEST_TABSHIELD")
      (footprint "eagle-import:PCB_SHIELD_TAB")
      (libsource (lib "eagle-import") (part "PCB_TEST_TABSHIELD"))
    )
    (comp (ref "TP4")
      (value "PCB_TEST_TABSHIELD")
      (footprint "eagle-import:PCB_SHIELD_TAB")
      (libsource (lib "eagle-import") (part "PCB_TEST_TABSHIELD"))
    )
    (comp (ref "TP5")
      (value "PCB_TEST_TABSHIELD")
      (footprint "eagle-import:PCB_SHIELD_TAB")
      (libsource (lib "eagle-import") (part "PCB_TEST_TABSHIELD"))
    )
    (comp (ref "TP6")
      (value "PCB_TEST_TABSHIELD")
      (footprint "eagle-import:PCB_SHIELD_TAB")
      (libsource (lib "eagle-import") (part "PCB_TEST_TABSHIELD"))
    )
    (comp (ref "TR2")
      (value "53100C")
      (footprint "eagle-import:MURATA_5300")
      (libsource (lib "eagle-import") (part "MURATA_5300"))
    )
    (comp (ref "TR3")
      (value "VAC T60006-L2025-W380")
      (footprint "eagle-import:VAC_DUAL_SEC")
      (libsource (lib "eagle-import") (part "PCB_TRAFO_FLYBACK2-VAC"))
    )
    (comp (ref "ZD4")
      (value "MMSZ5V1T1G")
      (footprint "eagle-import:SOD323-W")
      (libsource (lib "eagle-import") (part "ZENER-DIODESOD323"))
    )
    (comp (ref "ZD5")
      (value "PDZ6.2B")
      (footprint "eagle-import:SOD323-W")
      (libsource (lib "eagle-import") (part "ZENER-DIODESOD323"))
    )
  )
  (nets
    (net (code "1") (name "+6V") (class "Default")
      (node (ref "C22") (pin "1") (pinfunction "1_1") (pintype "passive"))
      (node (ref "C25") (pin "1") (pinfunction "1_1") (pintype "passive"))
      (node (ref "D7") (pin "C") (pinfunction "C_C") (pintype "passive"))
      (node (ref "IC2") (pin "8") (pinfunction "IN_8") (pintype "power_in"))
      (node (ref "L4") (pin "2") (pinfunction "2_2") (pintype "passive"))
      (node (ref "LED1") (pin "A") (pinfunction "A_A") (pintype "passive"))
      (node (ref "R22") (pin "2") (pinfunction "2_2") (pintype "passive"))
      (node (ref "R59") (pin "1") (pinfunction "1_1") (pintype "passive"))
    )
    (net (code "2") (name "+12V") (class "Default")
      (node (ref "C29") (pin "2") (pinfunction "2_2") (pintype "passive"))
      (node (ref "C30") (pin "2") (pinfunction "2_2") (pintype "passive"))
      (node (ref "C4") (pin "1") (pinfunction "1_1") (pintype "passive"))
      (node (ref "Q1") (pin "3") (pinfunction "E_3") (pintype "passive"))
      (node (ref "R26") (pin "2") (pinfunction "2_2") (pintype "passive"))
      (node (ref "R36") (pin "2") (pinfunction "2_2") (pintype "passive"))
      (node (ref "R43") (pin "2") (pinfunction "2_2") (pintype "passive"))
      (node (ref "X1") (pin "1") (pinfunction "1_1") (pintype "passive"))
    )
    (net (code "3") (name "0V") (class "Default")
      (node (ref "C13") (pin "-") (pinfunction "-_-") (pintype "passive"))
      (node (ref "C20") (pin "1") (pinfunction "1_1") (pintype "passive"))
      (node (ref "C27") (pin "2") (pinfunction "2_2") (pintype "passive"))
      (node (ref "C28") (pin "2") (pinfunction "2_2") (pintype "passive"))
      (node (ref "C29") (pin "1") (pinfunction "1_1") (pintype "passive"))
      (node (ref "C30") (pin "1") (pinfunction "1_1") (pintype "passive"))
      (node (ref "C31") (pin "-") (pinfunction "-_-") (pintype "passive"))
      (node (ref "C32") (pin "-") (pinfunction "-_-") (pintype "passive"))
      (node (ref "C36") (pin "1") (pinfunction "1_1") (pintype "passive"))
      (node (ref "C38") (pin "2") (pinfunction "2_2") (pintype "passive"))
      (node (ref "C39") (pin "2") (pinfunction "2_2") (pintype "passive"))
      (node (ref "C4") (pin "2") (pinfunction "2_2") (pintype "passive"))
      (node (ref "C40") (pin "2") (pinfunction "2_2") (pintype "passive"))
      (node (ref "C43") (pin "2") (pinfunction "2_2") (pintype "passive"))
      (node (ref "C44") (pin "2") (pinfunction "2_2") (pintype "passive"))
      (node (ref "C46") (pin "1") (pinfunction "1_1") (pintype "passive"))
      (node (ref "C47") (pin "1") (pinfunction "1_1") (pintype "passive"))
      (node (ref "C7") (pin "2") (pinfunction "-_2") (pintype "passive"))
      (node (ref "C8") (pin "2") (pinfunction "2_2") (pintype "passive"))
      (node (ref "D11") (pin "A") (pinfunction "A_A") (pintype "passive"))
      (node (ref "D15") (pin "2") (pinfunction "A_2") (pintype "passive"))
      (node (ref "IC3") (pin "1") (pinfunction "GND_1") (pintype "passive"))
      (node (ref "IC3") (pin "2") (pinfunction "GND_2") (pintype "passive"))
      (node (ref "IC3") (pin "3") (pinfunction "GND_3") (pintype "passive"))
      (node (ref "IC3") (pin "4") (pinfunction "GND_4") (pintype "passive"))
      (node (ref "IC4") (pin "9") (pinfunction "GNDB_9") (pintype "power_in"))
      (node (ref "JP2") (pin "NC") (pinfunction "NC_NC") (pintype "passive"))
      (node (ref "JP3") (pin "1") (pinfunction "1_1") (pintype "passive"))
      (node (ref "OK1") (pin "3") (pinfunction "EMIT_3") (pintype "passive"))
      (node (ref "Q3") (pin "S") (pinfunction "S_S") (pintype "passive"))
      (node (ref "Q4") (pin "S") (pinfunction "S_S") (pintype "passive"))
      (node (ref "Q5") (pin "S") (pinfunction "S_S") (pintype "passive"))
      (node (ref "R19") (pin "1") (pinfunction "1_1") (pintype "passive"))
      (node (ref "R20") (pin "2") (pinfunction "2_2") (pintype "passive"))
      (node (ref "R21") (pin "2") (pinfunction "2_2") (pintype "passive"))
      (node (ref "R37") (pin "2") (pinfunction "2_2") (pintype "passive"))
      (node (ref "R39") (pin "1") (pinfunction "1_1") (pintype "passive"))
      (node (ref "R39") (pin "2") (pinfunction "2_2") (pintype "passive"))
      (node (ref "SH1") (pin "P$2") (pinfunction "GND_B_P$2") (pintype "bidirectional"))
      (node (ref "TP1") (pin "1") (pinfunction "P$1_1") (pintype "bidirectional"))
      (node (ref "TP4") (pin "1") (pinfunction "P$1_1") (pintype "bidirectional"))
      (node (ref "TR1") (pin "6") (pinfunction "S_BIAS_6") (pintype "passive"))
      (node (ref "X1") (pin "2") (pinfunction "1_2") (pintype "passive"))
      (node (ref "ZD1") (pin "A") (pinfunction "A_A") (pintype "passive"))
      (node (ref "ZD2") (pin "A") (pinfunction "A_A") (pintype "passive"))
    )
    (net (code "4") (name "AGND") (class "Default")
      (node (ref "C37") (pin "1") (pinfunction "1_1") (pintype "passive"))
      (node (ref "C42") (pin "2") (pinfunction "2_2") (pintype "passive"))
      (node (ref "C45") (pin "1") (pinfunction "1_1") (pintype "passive"))
      (node (ref "C48") (pin "1") (pinfunction "1_1") (pintype "passive"))
      (node (ref "C49") (pin "1") (pinfunction "1_1") (pintype "passive"))
      (node (ref "C50") (pin "1") (pinfunction "1_1") (pintype "passive"))
      (node (ref "C51") (pin "1") (pinfunction "1_1") (pintype "passive"))
      (node (ref "IC4") (pin "4") (pinfunction "GNDI_4") (pintype "power_in"))
      (node (ref "IC4") (pin "5") (pinfunction "DISABLE_5") (pintype "input"))
      (node (ref "IC5") (pin "10") (pinfunction "PGND_10") (pintype "power_in"))
      (node (ref "IC5") (pin "11") (pinfunction "AGND_11") (pintype "power_in"))
      (node (ref "IC5") (pin "2") (pinfunction "FB_2") (pintype "input"))
      (node (ref "JP3") (pin "2") (pinfunction "2_2") (pintype "passive"))
      (node (ref "OK2") (pin "3") (pinfunction "EMIT_3") (pintype "passive"))
      (node (ref "Q6") (pin "C") (pinfunction "C_C") (pintype "passive"))
      (node (ref "R23") (pin "2") (pinfunction "2_2") (pintype "passive"))
      (node (ref "R24") (pin "2") (pinfunction "2_2") (pintype "passive"))
      (node (ref "R25") (pin "2") (pinfunction "2_2") (pintype "passive"))
      (node (ref "R32") (pin "1") (pinfunction "1_1") (pintype "passive"))
      (node (ref "R32") (pin "2") (pinfunction "2_2") (pintype "passive"))
      (node (ref "R33") (pin "1") (pinfunction "1_1") (pintype "passive"))
      (node (ref "R45") (pin "2") (pinfunction "2_2") (pintype "passive"))
      (node (ref "R48") (pin "2") (pinfunction "2_2") (pintype "passive"))
      (node (ref "R49") (pin "2") (pinfunction "2_2") (pintype "passive"))
      (node (ref "R52") (pin "2") (pinfunction "2_2") (pintype "passive"))
      (node (ref "TR2") (pin "1") (pinfunction "S_DOT_1") (pintype "passive"))
      (node (ref "ZD4") (pin "A") (pinfunction "A_A") (pintype "passive"))
      (node (ref "ZD5") (pin "A") (pinfunction "A_A") (pintype "passive"))
    )
    (net (code "5") (name "AUX") (class "Default")
      (node (ref "C3") (pin "2") (pinfunction "2_2") (pintype "passive"))
      (node (ref "D1") (pin "A") (pinfunction "A_A") (pintype "passive"))
      (node (ref "D10") (pin "A") (pinfunction "A_A") (pintype "passive"))
      (node (ref "R15") (pin "2") (pinfunction "2_2") (pintype "passive"))
      (node (ref "TR1") (pin "7") (pinfunction "S_BIAS_DOT_7") (pintype "passive"))
    )
    (net (code "6") (name "AUX_OUT") (class "Default")
      (node (ref "C20") (pin "2") (pinfunction "2_2") (pintype "passive"))
      (node (ref "C7") (pin "1") (pinfunction "+_1") (pintype "passive"))
      (node (ref "IC3") (pin "5") (pinfunction "VDD_5") (pintype "power_in"))
      (node (ref "Q1") (pin "2") (pinfunction "C_2") (pintype "passive"))
      (node (ref "Q1") (pin "4") (pinfunction "C_4") (pintype "passive"))
      (node (ref "R4") (pin "2") (pinfunction "2_2") (pintype "passive"))
      (node (ref "R5") (pin "1") (pinfunction "1_1") (pintype "passive"))
      (node (ref "ZD1") (pin "C") (pinfunction "C_C") (pintype "passive"))
    )
    (net (code "7") (name "BUCK_OUT") (class "Default")
      (node (ref "C33") (pin "2") (pinfunction "2_2") (pintype "passive"))
      (node (ref "C34") (pin "2") (pinfunction "2_2") (pintype "passive"))
      (node (ref "C35") (pin "2") (pinfunction "2_2") (pintype "passive"))
      (node (ref "D15") (pin "1") (pinfunction "C_1") (pintype "passive"))
      (node (ref "IC4") (pin "14") (pinfunction "GNDA_14") (pintype "power_in"))
      (node (ref "L5") (pin "2") (pinfunction "P$2_2") (pintype "bidirectional"))
      (node (ref "L6") (pin "2") (pinfunction "P$2_2") (pintype "bidirectional"))
      (node (ref "Q2") (pin "S") (pinfunction "S_S") (pintype "passive"))
      (node (ref "Q3") (pin "D") (pinfunction "D_D") (pintype "passive"))
      (node (ref "TP3") (pin "1") (pinfunction "P$1_1") (pintype "bidirectional"))
    )
    (net (code "8") (name "CT_OUT") (class "Default")
      (node (ref "D12") (pin "C") (pinfunction "C_C") (pintype "passive"))
      (node (ref "R24") (pin "1") (pinfunction "1_1") (pintype "passive"))
      (node (ref "R25") (pin "1") (pinfunction "1_1") (pintype "passive"))
      (node (ref "R51") (pin "1") (pinfunction "1_1") (pintype "passive"))
    )
    (net (code "9") (name "DC_BUS") (class "Default")
      (node (ref "B1") (pin "+") (pinfunction "+_+") (pintype "passive"))
      (node (ref "C12") (pin "1") (pinfunction "1_1") (pintype "passive"))
      (node (ref "C13") (pin "+") (pinfunction "+_+") (pintype "passive"))
      (node (ref "C31") (pin "+") (pinfunction "+_+") (pintype "passive"))
      (node (ref "C32") (pin "+") (pinfunction "+_+") (pintype "passive"))
      (node (ref "C36") (pin "2") (pinfunction "2_2") (pintype "passive"))
      (node (ref "R38") (pin "1") (pinfunction "1_1") (pintype "passive"))
      (node (ref "R40") (pin "2") (pinfunction "2_2") (pintype "passive"))
      (node (ref "R41") (pin "2") (pinfunction "2_2") (pintype "passive"))
      (node (ref "R7") (pin "1") (pinfunction "1_1") (pintype "passive"))
      (node (ref "R8") (pin "1") (pinfunction "1_1") (pintype "passive"))
      (node (ref "TR1") (pin "1") (pinfunction "SHIELD_1") (pintype "passive"))
      (node (ref "TR1") (pin "2") (pinfunction "P_2") (pintype "passive"))
      (node (ref "TR2") (pin "7") (pinfunction "P_7") (pintype "passive"))
    )
    (net (code "10") (name "DC_OUT") (class "Default")
      (node (ref "C11") (pin "1") (pinfunction "1_1") (pintype "passive"))
      (node (ref "L2") (pin "2") (pinfunction "2_2") (pintype "passive"))
      (node (ref "X3") (pin "3") (pinfunction "S_3") (pintype "passive"))
    )
    (net (code "11") (name "GND") (class "Default")
      (node (ref "C14") (pin "1") (pinfunction "+_1") (pintype "passive"))
      (node (ref "C15") (pin "1") (pinfunction "1_1") (pintype "passive"))
      (node (ref "C16") (pin "1") (pinfunction "1_1") (pintype "passive"))
      (node (ref "C17") (pin "1") (pinfunction "1_1") (pintype "passive"))
      (node (ref "C19") (pin "2") (pinfunction "2_2") (pintype "passive"))
      (node (ref "C22") (pin "2") (pinfunction "2_2") (pintype "passive"))
      (node (ref "C23") (pin "-") (pinfunction "-_-") (pintype "passive"))
      (node (ref "C24") (pin "-") (pinfunction "-_-") (pintype "passive"))
      (node (ref "C25") (pin "2") (pinfunction "2_2") (pintype "passive"))
      (node (ref "C52") (pin "-") (pinfunction "-_-") (pintype "passive"))
      (node (ref "C53") (pin "-") (pinfunction "-_-") (pintype "passive"))
      (node (ref "C54") (pin "-") (pinfunction "-_-") (pintype "passive"))
      (node (ref "C55") (pin "2") (pinfunction "2_2") (pintype "passive"))
      (node (ref "C56") (pin "2") (pinfunction "2_2") (pintype "passive"))
      (node (ref "C57") (pin "2") (pinfunction "2_2") (pintype "passive"))
      (node (ref "C58") (pin "2") (pinfunction "2_2") (pintype "passive"))
      (node (ref "C59") (pin "2") (pinfunction "2_2") (pintype "passive"))
      (node (ref "C60") (pin "1") (pinfunction "1_1") (pintype "passive"))
      (node (ref "C61") (pin "2") (pinfunction "2_2") (pintype "passive"))
      (node (ref "C62") (pin "2") (pinfunction "2_2") (pintype "passive"))
      (node (ref "C63") (pin "2") (pinfunction "2_2") (pintype "passive"))
      (node (ref "C64") (pin "2") (pinfunction "2_2") (pintype "passive"))
      (node (ref "C65") (pin "2") (pinfunction "2_2") (pintype "passive"))
      (node (ref "C66") (pin "2") (pinfunction "2_2") (pintype "passive"))
      (node (ref "C67") (pin "2") (pinfunction "2_2") (pintype "passive"))
      (node (ref "C71") (pin "-") (pinfunction "-_-") (pintype "passive"))
      (node (ref "C72") (pin "2") (pinfunction "2_2") (pintype "passive"))
      (node (ref "D3") (pin "C") (pinfunction "C_C") (pintype "passive"))
      (node (ref "D9") (pin "A") (pinfunction "A_A") (pintype "passive"))
      (node (ref "IC1") (pin "5") (pinfunction "GND_5") (pintype "passive"))
      (node (ref "IC2") (pin "4") (pinfunction "GND_4") (pintype "passive"))
      (node (ref "IC6") (pin "6") (pinfunction "VS_6") (pintype "passive"))
      (node (ref "IC6") (pin "7") (pinfunction "GND_7") (pintype "power_in"))
      (node (ref "IC7") (pin "3") (pinfunction "+IN_3") (pintype "input"))
      (node (ref "IC7") (pin "5") (pinfunction "+IN_5") (pintype "input"))
      (node (ref "IC8") (pin "4") (pinfunction "VCC-_4") (pintype "power_in"))
      (node (ref "IC9") (pin "3") (pinfunction "A_3") (pintype "passive"))
      (node (ref "JP1") (pin "NO") (pinfunction "NO_NO") (pintype "passive"))
      (node (ref "P1") (pin "A") (pinfunction "A_A") (pintype "passive"))
      (node (ref "Q7") (pin "2") (pinfunction "S_2") (pintype "passive"))
      (node (ref "Q8") (pin "2") (pinfunction "S_2") (pintype "passive"))
      (node (ref "R13") (pin "2") (pinfunction "2_2") (pintype "passive"))
      (node (ref "R14") (pin "2") (pinfunction "2_2") (pintype "passive"))
      (node (ref "R60") (pin "2") (pinfunction "2_2") (pintype "passive"))
      (node (ref "R80") (pin "1") (pinfunction "1_1") (pintype "passive"))
      (node (ref "TP2") (pin "1") (pinfunction "P$1_1") (pintype "bidirectional"))
      (node (ref "TP7") (pin "GND") (pinfunction "GND_GND") (pintype "bidirectional"))
      (node (ref "TR1") (pin "10") (pinfunction "S1_10") (pintype "passive"))
      (node (ref "TR1") (pin "11") (pinfunction "S1_11") (pintype "passive"))
      (node (ref "TR1") (pin "9") (pinfunction "S2_DOT_9") (pintype "passive"))
      (node (ref "X3") (pin "6") (pinfunction "S_6") (pintype "passive"))
      (node (ref "X4") (pin "2") (pinfunction "1_2") (pintype "passive"))
      (node (ref "ZD3") (pin "A") (pinfunction "A_A") (pintype "passive"))
      (node (ref "ZD6") (pin "A") (pinfunction "A_A") (pintype "passive"))
    )
    (net (code "12") (name "GNDA") (class "Default")
      (node (ref "B1") (pin "-") (pinfunction "-_-") (pintype "passive"))
      (node (ref "SH1") (pin "P$1") (pinfunction "GND_A_P$1") (pintype "bidirectional"))
    )
    (net (code "13") (name "HD") (class "Default")
      (node (ref "IC5") (pin "5") (pinfunction "HD_5") (pintype "output"))
      (node (ref "R28") (pin "2") (pinfunction "2_2") (pintype "passive"))
    )
    (net (code "14") (name "HI_OUT") (class "Default")
      (node (ref "D14") (pin "A") (pinfunction "A_A") (pintype "passive"))
      (node (ref "IC4") (pin "15") (pinfunction "VOA_15") (pintype "output"))
      (node (ref "R27") (pin "2") (pinfunction "2_2") (pintype "passive"))
    )
    (net (code "15") (name "ISO_FB") (class "Default")
      (node (ref "C50") (pin "2") (pinfunction "2_2") (pintype "passive"))
      (node (ref "IC5") (pin "3") (pinfunction "COMP_3") (pintype "passive"))
      (node (ref "OK2") (pin "4") (pinfunction "COL_4") (pintype "passive"))
      (node (ref "Q6") (pin "E") (pinfunction "E_E") (pintype "passive"))
      (node (ref "R53") (pin "1") (pinfunction "1_1") (pintype "passive"))
      (node (ref "TP6") (pin "1") (pinfunction "P$1_1") (pintype "bidirectional"))
    )
    (net (code "16") (name "LD") (class "Default")
      (node (ref "IC5") (pin "6") (pinfunction "LD_6") (pintype "output"))
      (node (ref "R30") (pin "2") (pinfunction "2_2") (pintype "passive"))
    )
    (net (code "17") (name "LO_OUT") (class "Default")
      (node (ref "D17") (pin "A") (pinfunction "A_A") (pintype "passive"))
      (node (ref "IC4") (pin "10") (pinfunction "VOB_10") (pintype "output"))
      (node (ref "R34") (pin "1") (pinfunction "1_1") (pintype "passive"))
    )
    (net (code "18") (name "Net-(C3-Pad1)") (class "Default")
      (node (ref "C3") (pin "1") (pinfunction "1_1") (pintype "passive"))
      (node (ref "R2") (pin "2") (pinfunction "2_2") (pintype "passive"))
    )
    (net (code "19") (name "Net-(C9-Pad1)") (class "Default")
      (node (ref "C9") (pin "1") (pinfunction "1_1") (pintype "passive"))
      (node (ref "R6") (pin "2") (pinfunction "2_2") (pintype "passive"))
    )
    (net (code "20") (name "Net-(C10-+)") (class "Default")
      (node (ref "C10") (pin "1") (pinfunction "+_1") (pintype "passive"))
      (node (ref "D2") (pin "C") (pinfunction "C_C") (pintype "passive"))
      (node (ref "L2") (pin "1") (pinfunction "1_1") (pintype "passive"))
      (node (ref "R6") (pin "1") (pinfunction "1_1") (pintype "passive"))
    )
    (net (code "21") (name "Net-(C10--)") (class "Default")
      (node (ref "C10") (pin "2") (pinfunction "-_2") (pintype "passive"))
      (node (ref "C11") (pin "2") (pinfunction "2_2") (pintype "passive"))
      (node (ref "JP1") (pin "COM") (pinfunction "COM_COM") (pintype "passive"))
      (node (ref "TR1") (pin "14") (pinfunction "S3_14") (pintype "passive"))
    )
    (net (code "22") (name "Net-(C12-Pad2)") (class "Default")
      (node (ref "C12") (pin "2") (pinfunction "2_2") (pintype "passive"))
      (node (ref "D4") (pin "C") (pinfunction "C_C") (pintype "passive"))
      (node (ref "R7") (pin "2") (pinfunction "2_2") (pintype "passive"))
    )
    (net (code "23") (name "Net-(C14--)") (class "Default")
      (node (ref "C14") (pin "2") (pinfunction "-_2") (pintype "passive"))
      (node (ref "D5") (pin "A") (pinfunction "A_A") (pintype "passive"))
      (node (ref "L3") (pin "1") (pinfunction "1_1") (pintype "passive"))
      (node (ref "R10") (pin "1") (pinfunction "1_1") (pintype "passive"))
    )
    (net (code "24") (name "Net-(C18-Pad1)") (class "Default")
      (node (ref "C18") (pin "1") (pinfunction "1_1") (pintype "passive"))
      (node (ref "R10") (pin "2") (pinfunction "2_2") (pintype "passive"))
    )
    (net (code "25") (name "Net-(C19-Pad1)") (class "Default")
      (node (ref "C19") (pin "1") (pinfunction "1_1") (pintype "passive"))
      (node (ref "JP2") (pin "COM") (pinfunction "COM_COM") (pintype "passive"))
    )
    (net (code "26") (name "Net-(C21-Pad1)") (class "Default")
      (node (ref "C21") (pin "1") (pinfunction "1_1") (pintype "passive"))
      (node (ref "R11") (pin "2") (pinfunction "2_2") (pintype "passive"))
    )
    (net (code "27") (name "Net-(C21-Pad2)") (class "Default")
      (node (ref "C21") (pin "2") (pinfunction "2_2") (pintype "passive"))
      (node (ref "D8") (pin "A") (pinfunction "A_A") (pintype "passive"))
      (node (ref "TR1") (pin "12") (pinfunction "S1_DOT_12") (pintype "passive"))
      (node (ref "TR1") (pin "13") (pinfunction "S1_DOT_13") (pintype "passive"))
    )
    (net (code "28") (name "Net-(C24-Pad+)") (class "Default")
      (node (ref "C24") (pin "+") (pinfunction "+_+") (pintype "passive"))
      (node (ref "D8") (pin "C") (pinfunction "C_C") (pintype "passive"))
      (node (ref "L4") (pin "1") (pinfunction "1_1") (pintype "passive"))
      (node (ref "R11") (pin "1") (pinfunction "1_1") (pintype "passive"))
      (node (ref "R18") (pin "1") (pinfunction "1_1") (pintype "passive"))
    )
    (net (code "29") (name "Net-(C26-Pad1)") (class "Default")
      (node (ref "C26") (pin "1") (pinfunction "1_1") (pintype "passive"))
      (node (ref "R21") (pin "1") (pinfunction "1_1") (pintype "passive"))
    )
    (net (code "30") (name "Net-(C41-Pad1)") (class "Default")
      (node (ref "C41") (pin "1") (pinfunction "1_1") (pintype "passive"))
      (node (ref "R31") (pin "1") (pinfunction "1_1") (pintype "passive"))
    )
    (net (code "31") (name "Net-(C46-Pad2)") (class "Default")
      (node (ref "C46") (pin "2") (pinfunction "2_2") (pintype "passive"))
      (node (ref "C47") (pin "2") (pinfunction "2_2") (pintype "passive"))
      (node (ref "D18") (pin "1") (pinfunction "C_1") (pintype "passive"))
      (node (ref "D18") (pin "3") (pinfunction "C_3") (pintype "passive"))
      (node (ref "D19") (pin "1") (pinfunction "C_1") (pintype "passive"))
      (node (ref "D19") (pin "3") (pinfunction "C_3") (pintype "passive"))
      (node (ref "R40") (pin "1") (pinfunction "1_1") (pintype "passive"))
      (node (ref "R41") (pin "1") (pinfunction "1_1") (pintype "passive"))
    )
    (net (code "32") (name "Net-(C51-Pad2)") (class "Default")
      (node (ref "C51") (pin "2") (pinfunction "2_2") (pintype "passive"))
      (node (ref "R53") (pin "2") (pinfunction "2_2") (pintype "passive"))
    )
    (net (code "33") (name "Net-(C60-Pad2)") (class "Default")
      (node (ref "C60") (pin "2") (pinfunction "2_2") (pintype "passive"))
      (node (ref "R55") (pin "1") (pinfunction "1_1") (pintype "passive"))
    )
    (net (code "34") (name "Net-(C61-Pad1)") (class "Default")
      (node (ref "C61") (pin "1") (pinfunction "1_1") (pintype "passive"))
      (node (ref "R56") (pin "2") (pinfunction "2_2") (pintype "passive"))
      (node (ref "R57") (pin "2") (pinfunction "2_2") (pintype "passive"))
    )
    (net (code "35") (name "Net-(C65-Pad1)") (class "Default")
      (node (ref "C65") (pin "1") (pinfunction "1_1") (pintype "passive"))
      (node (ref "R62") (pin "2") (pinfunction "2_2") (pintype "passive"))
      (node (ref "R63") (pin "2") (pinfunction "2_2") (pintype "passive"))
    )
    (net (code "36") (name "Net-(C70-Pad2)") (class "Default")
      (node (ref "C70") (pin "2") (pinfunction "2_2") (pintype "passive"))
      (node (ref "R74") (pin "2") (pinfunction "2_2") (pintype "passive"))
    )
    (net (code "37") (name "Net-(C71-Pad+)") (class "Default")
      (node (ref "C71") (pin "+") (pinfunction "+_+") (pintype "passive"))
      (node (ref "R67") (pin "1") (pinfunction "1_1") (pintype "passive"))
      (node (ref "R76") (pin "1") (pinfunction "1_1") (pintype "passive"))
      (node (ref "R77") (pin "1") (pinfunction "1_1") (pintype "passive"))
    )
    (net (code "38") (name "Net-(C74-Pad2)") (class "Default")
      (node (ref "C74") (pin "2") (pinfunction "2_2") (pintype "passive"))
      (node (ref "R79") (pin "1") (pinfunction "1_1") (pintype "passive"))
    )
    (net (code "39") (name "Net-(D1-PadC)") (class "Default")
      (node (ref "D1") (pin "C") (pinfunction "C_C") (pintype "passive"))
      (node (ref "R2") (pin "1") (pinfunction "1_1") (pintype "passive"))
      (node (ref "R4") (pin "1") (pinfunction "1_1") (pintype "passive"))
    )
    (net (code "40") (name "Net-(D10-PadC)") (class "Default")
      (node (ref "D10") (pin "C") (pinfunction "C_C") (pintype "passive"))
      (node (ref "D11") (pin "C") (pinfunction "C_C") (pintype "passive"))
      (node (ref "R17") (pin "2") (pinfunction "2_2") (pintype "passive"))
    )
    (net (code "41") (name "Net-(D13-A)") (class "Default")
      (node (ref "D13") (pin "2") (pinfunction "A_2") (pintype "passive"))
      (node (ref "R26") (pin "1") (pinfunction "1_1") (pintype "passive"))
    )
    (net (code "42") (name "Net-(D14-PadC)") (class "Default")
      (node (ref "D14") (pin "C") (pinfunction "C_C") (pintype "passive"))
      (node (ref "Q2") (pin "G") (pinfunction "G_G") (pintype "passive"))
      (node (ref "R27") (pin "1") (pinfunction "1_1") (pintype "passive"))
    )
    (net (code "43") (name "Net-(D16-PadA)") (class "Default")
      (node (ref "D16") (pin "A") (pinfunction "A_A") (pintype "passive"))
      (node (ref "R36") (pin "1") (pinfunction "1_1") (pintype "passive"))
    )
    (net (code "44") (name "Net-(D17-PadC)") (class "Default")
      (node (ref "D17") (pin "C") (pinfunction "C_C") (pintype "passive"))
      (node (ref "Q3") (pin "G") (pinfunction "G_G") (pintype "passive"))
      (node (ref "R34") (pin "2") (pinfunction "2_2") (pintype "passive"))
      (node (ref "R37") (pin "1") (pinfunction "1_1") (pintype "passive"))
    )
    (net (code "45") (name "Net-(D18-A)") (class "Default")
      (node (ref "C41") (pin "2") (pinfunction "2_2") (pintype "passive"))
      (node (ref "D18") (pin "2") (pinfunction "A_2") (pintype "passive"))
      (node (ref "L6") (pin "1") (pinfunction "P$1_1") (pintype "bidirectional"))
      (node (ref "Q5") (pin "D") (pinfunction "D_D") (pintype "passive"))
      (node (ref "TR3") (pin "P1_DOT") (pinfunction "P_DOT_P1_DOT") (pintype "passive"))
    )
    (net (code "46") (name "Net-(D19-A)") (class "Default")
      (node (ref "D19") (pin "2") (pinfunction "A_2") (pintype "passive"))
      (node (ref "L5") (pin "1") (pinfunction "P$1_1") (pintype "bidirectional"))
      (node (ref "Q4") (pin "D") (pinfunction "D_D") (pintype "passive"))
      (node (ref "R29") (pin "2") (pinfunction "2_2") (pintype "passive"))
      (node (ref "TR3") (pin "P1") (pinfunction "P_P1") (pintype "passive"))
    )
    (net (code "47") (name "Net-(D20-PadC)") (class "Default")
      (node (ref "D20") (pin "C") (pinfunction "C_C") (pintype "passive"))
      (node (ref "Q4") (pin "G") (pinfunction "G_G") (pintype "passive"))
      (node (ref "R46") (pin "1") (pinfunction "1_1") (pintype "passive"))
    )
    (net (code "48") (name "Net-(D21-PadC)") (class "Default")
      (node (ref "D21") (pin "C") (pinfunction "C_C") (pintype "passive"))
      (node (ref "Q5") (pin "G") (pinfunction "G_G") (pintype "passive"))
      (node (ref "R47") (pin "1") (pinfunction "1_1") (pintype "passive"))
    )
    (net (code "49") (name "Net-(IC2-FB)") (class "Default")
      (node (ref "IC2") (pin "7") (pinfunction "FB_7") (pintype "input"))
      (node (ref "R12") (pin "2") (pinfunction "2_2") (pintype "passive"))
      (node (ref "R13") (pin "1") (pinfunction "1_1") (pintype "passive"))
    )
    (net (code "50") (name "Net-(IC2-~{ERROR})") (class "Default")
      (node (ref "IC2") (pin "5") (pinfunction "~{ERROR}_5") (pintype "input"))
      (node (ref "R16") (pin "2") (pinfunction "2_2") (pintype "passive"))
      (node (ref "X3") (pin "4") (pinfunction "S_4") (pintype "passive"))
    )
    (net (code "51") (name "Net-(IC3-BR)") (class "Default")
      (node (ref "IC3") (pin "8") (pinfunction "BR_8") (pintype "input"))
      (node (ref "R20") (pin "1") (pinfunction "1_1") (pintype "passive"))
      (node (ref "R9") (pin "2") (pinfunction "2_2") (pintype "passive"))
    )
    (net (code "52") (name "Net-(IC3-FB)") (class "Default")
      (node (ref "C26") (pin "2") (pinfunction "2_2") (pintype "passive"))
      (node (ref "C28") (pin "1") (pinfunction "1_1") (pintype "passive"))
      (node (ref "IC3") (pin "7") (pinfunction "FB_7") (pintype "input"))
      (node (ref "OK1") (pin "4") (pinfunction "COL_4") (pintype "passive"))
    )
    (net (code "53") (name "Net-(IC3-ZCD)") (class "Default")
      (node (ref "C27") (pin "1") (pinfunction "1_1") (pintype "passive"))
      (node (ref "IC3") (pin "6") (pinfunction "ZCD_6") (pintype "input"))
      (node (ref "R15") (pin "1") (pinfunction "1_1") (pintype "passive"))
      (node (ref "R17") (pin "1") (pinfunction "1_1") (pintype "passive"))
      (node (ref "R19") (pin "2") (pinfunction "2_2") (pintype "passive"))
    )
    (net (code "54") (name "Net-(IC4-DT)") (class "Default")
      (node (ref "IC4") (pin "6") (pinfunction "DT_6") (pintype "input"))
      (node (ref "R33") (pin "2") (pinfunction "2_2") (pintype "passive"))
    )
    (net (code "55") (name "Net-(IC4-VDDA)") (class "Default")
      (node (ref "C33") (pin "1") (pinfunction "1_1") (pintype "passive"))
      (node (ref "C34") (pin "1") (pinfunction "1_1") (pintype "passive"))
      (node (ref "C35") (pin "1") (pinfunction "1_1") (pintype "passive"))
      (node (ref "D13") (pin "1") (pinfunction "C_1") (pintype "passive"))
      (node (ref "D13") (pin "3") (pinfunction "C_3") (pintype "passive"))
      (node (ref "IC4") (pin "16") (pinfunction "VDDA_16") (pintype "power_in"))
    )
    (net (code "56") (name "Net-(IC4-VDDB)") (class "Default")
      (node (ref "C38") (pin "1") (pinfunction "1_1") (pintype "passive"))
      (node (ref "C39") (pin "1") (pinfunction "1_1") (pintype "passive"))
      (node (ref "C40") (pin "1") (pinfunction "1_1") (pintype "passive"))
      (node (ref "D16") (pin "C") (pinfunction "C_C") (pintype "passive"))
      (node (ref "IC4") (pin "11") (pinfunction "VDDB_11") (pintype "power_in"))
    )
    (net (code "57") (name "Net-(IC4-VIA)") (class "Default")
      (node (ref "IC4") (pin "1") (pinfunction "VIA_1") (pintype "input"))
      (node (ref "R28") (pin "1") (pinfunction "1_1") (pintype "passive"))
    )
    (net (code "58") (name "Net-(IC4-VIB)") (class "Default")
      (node (ref "IC4") (pin "2") (pinfunction "VIB_2") (pintype "input"))
      (node (ref "R30") (pin "1") (pinfunction "1_1") (pintype "passive"))
    )
    (net (code "59") (name "Net-(IC5-CS)") (class "Default")
      (node (ref "C49") (pin "2") (pinfunction "2_2") (pintype "passive"))
      (node (ref "IC5") (pin "12") (pinfunction "CS_12") (pintype "input"))
      (node (ref "R51") (pin "2") (pinfunction "2_2") (pintype "passive"))
    )
    (net (code "60") (name "Net-(IC5-REF)") (class "Default")
      (node (ref "C48") (pin "2") (pinfunction "2_2") (pintype "passive"))
      (node (ref "IC5") (pin "4") (pinfunction "REF_4") (pintype "output"))
      (node (ref "R35") (pin "1") (pinfunction "1_1") (pintype "passive"))
      (node (ref "R50") (pin "1") (pinfunction "1_1") (pintype "passive"))
    )
    (net (code "61") (name "Net-(IC5-RT{slash}SYNC)") (class "Default")
      (node (ref "IC5") (pin "15") (pinfunction "RT/SYNC_15") (pintype "input"))
      (node (ref "R49") (pin "1") (pinfunction "1_1") (pintype "passive"))
    )
    (net (code "62") (name "Net-(IC5-SS)") (class "Default")
      (node (ref "C45") (pin "2") (pinfunction "2_2") (pintype "passive"))
      (node (ref "IC5") (pin "13") (pinfunction "SS_13") (pintype "passive"))
    )
    (net (code "63") (name "Net-(IC5-TIME)") (class "Default")
      (node (ref "IC5") (pin "14") (pinfunction "TIME_14") (pintype "input"))
      (node (ref "R48") (pin "1") (pinfunction "1_1") (pintype "passive"))
    )
    (net (code "64") (name "Net-(IC5-UVLO)") (class "Default")
      (node (ref "IC5") (pin "16") (pinfunction "UVLO_16") (pintype "input"))
      (node (ref "R44") (pin "1") (pinfunction "1_1") (pintype "passive"))
      (node (ref "ZD5") (pin "C") (pinfunction "C_C") (pintype "passive"))
    )
    (net (code "65") (name "Net-(IC5-VCC)") (class "Default")
      (node (ref "C43") (pin "1") (pinfunction "1_1") (pintype "passive"))
      (node (ref "C44") (pin "1") (pinfunction "1_1") (pintype "passive"))
      (node (ref "IC5") (pin "1") (pinfunction "VIN_1") (pintype "input"))
      (node (ref "IC5") (pin "7") (pinfunction "VCC_7") (pintype "power_in"))
      (node (ref "R43") (pin "1") (pinfunction "1_1") (pintype "passive"))
    )
    (net (code "66") (name "Net-(IC6-GATE1)") (class "Default")
      (node (ref "D22") (pin "C") (pinfunction "C_C") (pintype "passive"))
      (node (ref "IC6") (pin "1") (pinfunction "GATE1_1") (pintype "output"))
      (node (ref "R58") (pin "2") (pinfunction "2_2") (pintype "passive"))
    )
    (net (code "67") (name "Net-(IC6-GATE2)") (class "Default")
      (node (ref "D23") (pin "C") (pinfunction "C_C") (pintype "passive"))
      (node (ref "IC6") (pin "8") (pinfunction "GATE2_8") (pintype "output"))
      (node (ref "R61") (pin "2") (pinfunction "2_2") (pintype "passive"))
    )
    (net (code "68") (name "Net-(IC6-MOT)") (class "Default")
      (node (ref "IC6") (pin "3") (pinfunction "MOT_3") (pintype "passive"))
      (node (ref "R60") (pin "1") (pinfunction "1_1") (pintype "passive"))
    )
    (net (code "69") (name "Net-(IC6-VCC)") (class "Default")
      (node (ref "C62") (pin "1") (pinfunction "1_1") (pintype "passive"))
      (node (ref "C63") (pin "1") (pinfunction "1_1") (pintype "passive"))
      (node (ref "IC6") (pin "2") (pinfunction "VCC_2") (pintype "power_in"))
      (node (ref "R59") (pin "2") (pinfunction "2_2") (pintype "passive"))
    )
    (net (code "70") (name "Net-(IC7A--IN)") (class "Default")
      (node (ref "C68") (pin "2") (pinfunction "2_2") (pintype "passive"))
      (node (ref "IC7") (pin "2") (pinfunction "-IN_2") (pintype "input"))
      (node (ref "R68") (pin "2") (pinfunction "2_2") (pintype "passive"))
      (node (ref "R69") (pin "1") (pinfunction "1_1") (pintype "passive"))
      (node (ref "R73") (pin "1") (pinfunction "1_1") (pintype "passive"))
    )
    (net (code "71") (name "Net-(IC7A-OUT)") (class "Default")
      (node (ref "C68") (pin "1") (pinfunction "1_1") (pintype "passive"))
      (node (ref "IC7") (pin "1") (pinfunction "OUT_1") (pintype "output"))
      (node (ref "R77") (pin "2") (pinfunction "2_2") (pintype "passive"))
    )
    (net (code "72") (name "Net-(IC7B--IN)") (class "Default")
      (node (ref "IC7") (pin "6") (pinfunction "-IN_6") (pintype "input"))
      (node (ref "R64") (pin "2") (pinfunction "2_2") (pintype "passive"))
      (node (ref "R66") (pin "1") (pinfunction "1_1") (pintype "passive"))
    )
    (net (code "73") (name "Net-(IC7B-OUT)") (class "Default")
      (node (ref "IC7") (pin "7") (pinfunction "OUT_7") (pintype "output"))
      (node (ref "R64") (pin "1") (pinfunction "1_1") (pintype "passive"))
      (node (ref "R69") (pin "2") (pinfunction "2_2") (pintype "passive"))
    )
    (net (code "74") (name "Net-(IC8A-+IN1)") (class "Default")
      (node (ref "C72") (pin "1") (pinfunction "1_1") (pintype "passive"))
      (node (ref "IC8") (pin "3") (pinfunction "+IN1_3") (pintype "input"))
      (node (ref "P1") (pin "E") (pinfunction "E_E") (pintype "passive"))
      (node (ref "R66") (pin "2") (pinfunction "2_2") (pintype "passive"))
      (node (ref "R72") (pin "1") (pinfunction "1_1") (pintype "passive"))
    )
    (net (code "75") (name "Net-(IC8A--IN1)") (class "Default")
      (node (ref "C69") (pin "2") (pinfunction "2_2") (pintype "passive"))
      (node (ref "IC8") (pin "2") (pinfunction "-IN1_2") (pintype "input"))
      (node (ref "R74") (pin "1") (pinfunction "1_1") (pintype "passive"))
      (node (ref "R75") (pin "1") (pinfunction "1_1") (pintype "passive"))
    )
    (net (code "76") (name "Net-(IC8A-OUT1)") (class "Default")
      (node (ref "C69") (pin "1") (pinfunction "1_1") (pintype "passive"))
      (node (ref "C70") (pin "1") (pinfunction "1_1") (pintype "passive"))
      (node (ref "C73") (pin "1") (pinfunction "1_1") (pintype "passive"))
      (node (ref "C74") (pin "1") (pinfunction "1_1") (pintype "passive"))
      (node (ref "IC8") (pin "1") (pinfunction "OUT1_1") (pintype "output"))
      (node (ref "IC9") (pin "1") (pinfunction "C_1") (pintype "passive"))
      (node (ref "OK2") (pin "2") (pinfunction "C_2") (pintype "passive"))
      (node (ref "R78") (pin "2") (pinfunction "2_2") (pintype "passive"))
    )
    (net (code "77") (name "Net-(IC8B-+IN)") (class "Default")
      (node (ref "IC8") (pin "5") (pinfunction "+IN_5") (pintype "input"))
      (node (ref "JP4") (pin "COM") (pinfunction "COM_COM") (pintype "passive"))
    )
    (net (code "78") (name "Net-(IC8B--IN)") (class "Default")
      (node (ref "IC8") (pin "6") (pinfunction "-IN_6") (pintype "input"))
      (node (ref "IC8") (pin "7") (pinfunction "OUT_7") (pintype "output"))
      (node (ref "R73") (pin "2") (pinfunction "2_2") (pintype "passive"))
    )
    (net (code "79") (name "Net-(IC9-REF)") (class "Default")
      (node (ref "C73") (pin "2") (pinfunction "2_2") (pintype "passive"))
      (node (ref "IC9") (pin "2") (pinfunction "REF_2") (pintype "passive"))
      (node (ref "R71") (pin "1") (pinfunction "1_1") (pintype "passive"))
      (node (ref "R75") (pin "2") (pinfunction "2_2") (pintype "passive"))
      (node (ref "R76") (pin "2") (pinfunction "2_2") (pintype "passive"))
      (node (ref "R79") (pin "2") (pinfunction "2_2") (pintype "passive"))
      (node (ref "R80") (pin "2") (pinfunction "2_2") (pintype "passive"))
      (node (ref "TP8") (pin "1") (pinfunction "P$1_1") (pintype "bidirectional"))
    )
    (net (code "80") (name "Net-(JP4-PadNO)") (class "Default")
      (node (ref "JP4") (pin "NO") (pinfunction "NO_NO") (pintype "passive"))
      (node (ref "P1") (pin "S") (pinfunction "S_S") (pintype "passive"))
    )
    (net (code "81") (name "Net-(L1B-1)") (class "Default")
      (node (ref "B1") (pin "AC2") (pinfunction "AC2_AC2") (pintype "passive"))
      (node (ref "C2") (pin "2") (pinfunction "2_2") (pintype "passive"))
      (node (ref "C5") (pin "2") (pinfunction "2_2") (pintype "passive"))
      (node (ref "L1") (pin "3") (pinfunction "1_3") (pintype "passive"))
      (node (ref "SAR2") (pin "2") (pinfunction "P$2_2") (pintype "bidirectional"))
    )
    (net (code "82") (name "Net-(L1B-2)") (class "Default")
      (node (ref "C1") (pin "2") (pinfunction "2_2") (pintype "passive"))
      (node (ref "L1") (pin "4") (pinfunction "2_4") (pintype "passive"))
      (node (ref "R3") (pin "2") (pinfunction "2_2") (pintype "passive"))
      (node (ref "SAR2") (pin "1") (pinfunction "P$1_1") (pintype "bidirectional"))
      (node (ref "X2") (pin "3") (pinfunction "1_3") (pintype "passive"))
    )
    (net (code "83") (name "Net-(LED1-PadC)") (class "Default")
      (node (ref "LED1") (pin "C") (pinfunction "C_C") (pintype "passive"))
      (node (ref "R14") (pin "1") (pinfunction "1_1") (pintype "passive"))
    )
    (net (code "84") (name "Net-(OK1-A)") (class "Default")
      (node (ref "OK1") (pin "1") (pinfunction "A_1") (pintype "passive"))
      (node (ref "R18") (pin "2") (pinfunction "2_2") (pintype "passive"))
    )
    (net (code "85") (name "Net-(OK1-C)") (class "Default")
      (node (ref "OK1") (pin "2") (pinfunction "C_2") (pintype "passive"))
      (node (ref "R22") (pin "1") (pinfunction "1_1") (pintype "passive"))
      (node (ref "ZD3") (pin "C") (pinfunction "C_C") (pintype "passive"))
    )
    (net (code "86") (name "Net-(OK2-A)") (class "Default")
      (node (ref "OK2") (pin "1") (pinfunction "A_1") (pintype "passive"))
      (node (ref "R70") (pin "1") (pinfunction "1_1") (pintype "passive"))
      (node (ref "R78") (pin "1") (pinfunction "1_1") (pintype "passive"))
    )
    (net (code "87") (name "Net-(Q1-B)") (class "Default")
      (node (ref "C8") (pin "1") (pinfunction "1_1") (pintype "passive"))
      (node (ref "Q1") (pin "1") (pinfunction "B_1") (pintype "passive"))
      (node (ref "R5") (pin "2") (pinfunction "2_2") (pintype "passive"))
      (node (ref "ZD2") (pin "C") (pinfunction "C_C") (pintype "passive"))
    )
    (net (code "88") (name "Net-(Q6-PadB)") (class "Default")
      (node (ref "Q6") (pin "B") (pinfunction "B_B") (pintype "passive"))
      (node (ref "R50") (pin "2") (pinfunction "2_2") (pintype "passive"))
      (node (ref "R52") (pin "1") (pinfunction "1_1") (pintype "passive"))
    )
    (net (code "89") (name "Net-(R1-Pad2)") (class "Default")
      (node (ref "R1") (pin "2") (pinfunction "2_2") (pintype "passive"))
      (node (ref "R3") (pin "1") (pinfunction "1_1") (pintype "passive"))
    )
    (net (code "90") (name "Net-(R8-Pad2)") (class "Default")
      (node (ref "R8") (pin "2") (pinfunction "2_2") (pintype "passive"))
      (node (ref "R9") (pin "1") (pinfunction "1_1") (pintype "passive"))
    )
    (net (code "91") (name "Net-(R29-Pad1)") (class "Default")
      (node (ref "R29") (pin "1") (pinfunction "1_1") (pintype "passive"))
      (node (ref "R31") (pin "2") (pinfunction "2_2") (pintype "passive"))
    )
    (net (code "92") (name "Net-(R38-Pad2)") (class "Default")
      (node (ref "R38") (pin "2") (pinfunction "2_2") (pintype "passive"))
      (node (ref "R42") (pin "1") (pinfunction "1_1") (pintype "passive"))
    )
    (net (code "93") (name "Net-(R65-Pad1)") (class "Default")
      (node (ref "R65") (pin "1") (pinfunction "1_1") (pintype "passive"))
      (node (ref "R71") (pin "2") (pinfunction "2_2") (pintype "passive"))
    )
    (net (code "94") (name "Net-(R67-Pad2)") (class "Default")
      (node (ref "R67") (pin "2") (pinfunction "2_2") (pintype "passive"))
      (node (ref "R68") (pin "1") (pinfunction "1_1") (pintype "passive"))
    )
    (net (code "95") (name "Net-(SAR1-P$1)") (class "Default")
      (node (ref "C1") (pin "1") (pinfunction "1_1") (pintype "passive"))
      (node (ref "L1") (pin "2") (pinfunction "2_2") (pintype "passive"))
      (node (ref "R1") (pin "1") (pinfunction "1_1") (pintype "passive"))
      (node (ref "SAR1") (pin "1") (pinfunction "P$1_1") (pintype "bidirectional"))
      (node (ref "X2") (pin "2") (pinfunction "1_2") (pintype "passive"))
    )
    (net (code "96") (name "Net-(SAR1-P$2)") (class "Default")
      (node (ref "B1") (pin "AC1") (pinfunction "AC1_AC1") (pintype "passive"))
      (node (ref "C2") (pin "1") (pinfunction "1_1") (pintype "passive"))
      (node (ref "C6") (pin "2") (pinfunction "2_2") (pintype "passive"))
      (node (ref "L1") (pin "1") (pinfunction "1_1") (pintype "passive"))
      (node (ref "SAR1") (pin "2") (pinfunction "P$2_2") (pintype "bidirectional"))
    )
    (net (code "97") (name "Net-(TP5-P$1)") (class "Default")
      (node (ref "C42") (pin "1") (pinfunction "1_1") (pintype "passive"))
      (node (ref "R42") (pin "2") (pinfunction "2_2") (pintype "passive"))
      (node (ref "R44") (pin "2") (pinfunction "2_2") (pintype "passive"))
      (node (ref "R45") (pin "1") (pinfunction "1_1") (pintype "passive"))
      (node (ref "TP5") (pin "1") (pinfunction "P$1_1") (pintype "bidirectional"))
    )
    (net (code "98") (name "Net-(TR1-P2_DOT)") (class "Default")
      (node (ref "D4") (pin "A") (pinfunction "A_A") (pintype "passive"))
      (node (ref "IC3") (pin "13") (pinfunction "DRAIN_13") (pintype "output"))
      (node (ref "IC3") (pin "14") (pinfunction "DRAIN_14") (pintype "output"))
      (node (ref "IC3") (pin "15") (pinfunction "DRAIN_15") (pintype "output"))
      (node (ref "IC3") (pin "16") (pinfunction "DRAIN_16") (pintype "output"))
      (node (ref "TR1") (pin "4") (pinfunction "P2_DOT_4") (pintype "passive"))
    )
    (net (code "99") (name "Net-(TR1-S2)") (class "Default")
      (node (ref "C18") (pin "2") (pinfunction "2_2") (pintype "passive"))
      (node (ref "D5") (pin "C") (pinfunction "C_C") (pintype "passive"))
      (node (ref "TR1") (pin "8") (pinfunction "S2_8") (pintype "passive"))
    )
    (net (code "100") (name "Net-(TR1-S3_DOT)") (class "Default")
      (node (ref "C9") (pin "2") (pinfunction "2_2") (pintype "passive"))
      (node (ref "D2") (pin "A") (pinfunction "A_A") (pintype "passive"))
      (node (ref "TR1") (pin "15") (pinfunction "S3_DOT_15") (pintype "passive"))
    )
    (net (code "101") (name "Net-(TR2-P_DOT)") (class "Default")
      (node (ref "Q2") (pin "D") (pinfunction "D_D") (pintype "passive"))
      (node (ref "TR2") (pin "8") (pinfunction "P_DOT_8") (pintype "passive"))
    )
    (net (code "102") (name "Net-(TR2-S)") (class "Default")
      (node (ref "D12") (pin "A") (pinfunction "A_A") (pintype "passive"))
      (node (ref "R23") (pin "1") (pinfunction "1_1") (pintype "passive"))
      (node (ref "TR2") (pin "3") (pinfunction "S_3") (pintype "passive"))
    )
    (net (code "103") (name "Net-(X3H-S)") (class "Default")
      (node (ref "C15") (pin "2") (pinfunction "2_2") (pintype "passive"))
      (node (ref "C16") (pin "2") (pinfunction "2_2") (pintype "passive"))
      (node (ref "D6") (pin "A") (pinfunction "A_A") (pintype "passive"))
      (node (ref "IC1") (pin "2") (pinfunction "IN_2") (pintype "input"))
      (node (ref "IC1") (pin "3") (pinfunction "IN_3") (pintype "input"))
      (node (ref "IC1") (pin "6") (pinfunction "IN_6") (pintype "input"))
      (node (ref "IC1") (pin "7") (pinfunction "IN_7") (pintype "input"))
      (node (ref "L3") (pin "2") (pinfunction "2_2") (pintype "passive"))
      (node (ref "X3") (pin "8") (pinfunction "S_8") (pintype "passive"))
    )
    (net (code "104") (name "PE") (class "Default")
      (node (ref "C5") (pin "1") (pinfunction "1_1") (pintype "passive"))
      (node (ref "C6") (pin "1") (pinfunction "1_1") (pintype "passive"))
      (node (ref "JP2") (pin "NO") (pinfunction "NO_NO") (pintype "passive"))
      (node (ref "X2") (pin "1") (pinfunction "1_1") (pintype "passive"))
    )
    (net (code "105") (name "POUT+") (class "Default")
      (node (ref "C52") (pin "+") (pinfunction "+_+") (pintype "passive"))
      (node (ref "C53") (pin "+") (pinfunction "+_+") (pintype "passive"))
      (node (ref "C54") (pin "+") (pinfunction "+_+") (pintype "passive"))
      (node (ref "C55") (pin "1") (pinfunction "1_1") (pintype "passive"))
      (node (ref "L7") (pin "1") (pinfunction "1_1") (pintype "passive"))
      (node (ref "R54") (pin "1") (pinfunction "1_1") (pintype "passive"))
      (node (ref "R65") (pin "2") (pinfunction "2_2") (pintype "passive"))
      (node (ref "SH2") (pin "P$2") (pinfunction "GND_B_P$2") (pintype "bidirectional"))
      (node (ref "SH3") (pin "P$1") (pinfunction "GND_A_P$1") (pintype "bidirectional"))
    )
    (net (code "106") (name "PREG_OUT+") (class "Default")
      (node (ref "C56") (pin "1") (pinfunction "1_1") (pintype "passive"))
      (node (ref "C57") (pin "1") (pinfunction "1_1") (pintype "passive"))
      (node (ref "C58") (pin "1") (pinfunction "1_1") (pintype "passive"))
      (node (ref "C59") (pin "1") (pinfunction "1_1") (pintype "passive"))
      (node (ref "JP1") (pin "NC") (pinfunction "NC_NC") (pintype "passive"))
      (node (ref "L7") (pin "2") (pinfunction "2_2") (pintype "passive"))
      (node (ref "R54") (pin "2") (pinfunction "2_2") (pintype "passive"))
      (node (ref "R55") (pin "2") (pinfunction "2_2") (pintype "passive"))
      (node (ref "TP7") (pin "TIP") (pinfunction "TIP_TIP") (pintype "bidirectional"))
      (node (ref "X3") (pin "2") (pinfunction "S_2") (pintype "passive"))
      (node (ref "X4") (pin "1") (pinfunction "1_1") (pintype "passive"))
      (node (ref "ZD6") (pin "C") (pinfunction "C_C") (pintype "passive"))
    )
    (net (code "107") (name "PULL") (class "Default")
      (node (ref "D21") (pin "A") (pinfunction "A_A") (pintype "passive"))
      (node (ref "IC5") (pin "9") (pinfunction "PULL_9") (pintype "output"))
      (node (ref "R47") (pin "2") (pinfunction "2_2") (pintype "passive"))
    )
    (net (code "108") (name "PUSH") (class "Default")
      (node (ref "D20") (pin "A") (pinfunction "A_A") (pintype "passive"))
      (node (ref "IC5") (pin "8") (pinfunction "PUSH_8") (pintype "output"))
      (node (ref "R46") (pin "2") (pinfunction "2_2") (pintype "passive"))
    )
    (net (code "109") (name "REF") (class "Default")
      (node (ref "C37") (pin "2") (pinfunction "2_2") (pintype "passive"))
      (node (ref "IC4") (pin "3") (pinfunction "VDDI_3") (pintype "power_in"))
      (node (ref "IC4") (pin "8") (pinfunction "VDDI_8") (pintype "power_in"))
      (node (ref "R35") (pin "2") (pinfunction "2_2") (pintype "passive"))
      (node (ref "ZD4") (pin "C") (pinfunction "C_C") (pintype "passive"))
    )
    (net (code "110") (name "S1_DOT_OUT") (class "Default")
      (node (ref "IC6") (pin "4") (pinfunction "VD1_4") (pintype "passive"))
      (node (ref "Q7") (pin "3") (pinfunction "D_3") (pintype "passive"))
      (node (ref "R56") (pin "1") (pinfunction "1_1") (pintype "passive"))
      (node (ref "R57") (pin "1") (pinfunction "1_1") (pintype "passive"))
      (node (ref "TR3") (pin "S1_DOT") (pinfunction "S1_DOT_S1_DOT") (pintype "passive"))
    )
    (net (code "111") (name "S1_OUT") (class "Default")
      (node (ref "SH2") (pin "P$1") (pinfunction "GND_A_P$1") (pintype "bidirectional"))
      (node (ref "TR3") (pin "S1") (pinfunction "S1_S1") (pintype "passive"))
    )
    (net (code "112") (name "S2_DOT_OUT") (class "Default")
      (node (ref "SH3") (pin "P$2") (pinfunction "GND_B_P$2") (pintype "bidirectional"))
      (node (ref "TR3") (pin "S2_DOT") (pinfunction "S2_DOT_S2_DOT") (pintype "passive"))
    )
    (net (code "113") (name "S2_OUT") (class "Default")
      (node (ref "IC6") (pin "5") (pinfunction "VD2_5") (pintype "passive"))
      (node (ref "Q8") (pin "3") (pinfunction "D_3") (pintype "passive"))
      (node (ref "R62") (pin "1") (pinfunction "1_1") (pintype "passive"))
      (node (ref "R63") (pin "1") (pinfunction "1_1") (pintype "passive"))
      (node (ref "TR3") (pin "S2") (pinfunction "S2_S2") (pintype "passive"))
    )
    (net (code "114") (name "SR_OUT1") (class "Default")
      (node (ref "D22") (pin "A") (pinfunction "A_A") (pintype "passive"))
      (node (ref "Q7") (pin "1") (pinfunction "G_1") (pintype "passive"))
      (node (ref "R58") (pin "1") (pinfunction "1_1") (pintype "passive"))
    )
    (net (code "115") (name "SR_OUT2") (class "Default")
      (node (ref "D23") (pin "A") (pinfunction "A_A") (pintype "passive"))
      (node (ref "Q8") (pin "1") (pinfunction "G_1") (pintype "passive"))
      (node (ref "R61") (pin "1") (pinfunction "1_1") (pintype "passive"))
    )
    (net (code "116") (name "U_MON") (class "Default")
      (node (ref "JP4") (pin "NC") (pinfunction "NC_NC") (pintype "passive"))
      (node (ref "X3") (pin "1") (pinfunction "S_1") (pintype "passive"))
    )
    (net (code "117") (name "V+") (class "Default")
      (node (ref "C23") (pin "+") (pinfunction "+_+") (pintype "passive"))
      (node (ref "C64") (pin "1") (pinfunction "1_1") (pintype "passive"))
      (node (ref "C67") (pin "1") (pinfunction "1_1") (pintype "passive"))
      (node (ref "D7") (pin "A") (pinfunction "A_A") (pintype "passive"))
      (node (ref "D9") (pin "C") (pinfunction "C_C") (pintype "passive"))
      (node (ref "IC2") (pin "1") (pinfunction "OUT_1") (pintype "output"))
      (node (ref "IC7") (pin "8") (pinfunction "V+_8") (pintype "power_in"))
      (node (ref "IC8") (pin "8") (pinfunction "VCC+_8") (pintype "power_in"))
      (node (ref "R12") (pin "1") (pinfunction "1_1") (pintype "passive"))
      (node (ref "R16") (pin "1") (pinfunction "1_1") (pintype "passive"))
      (node (ref "R70") (pin "2") (pinfunction "2_2") (pintype "passive"))
      (node (ref "R72") (pin "2") (pinfunction "2_2") (pintype "passive"))
      (node (ref "X3") (pin "5") (pinfunction "S_5") (pintype "passive"))
    )
    (net (code "118") (name "V-") (class "Default")
      (node (ref "C17") (pin "2") (pinfunction "2_2") (pintype "passive"))
      (node (ref "C66") (pin "1") (pinfunction "1_1") (pintype "passive"))
      (node (ref "D3") (pin "A") (pinfunction "A_A") (pintype "passive"))
      (node (ref "D6") (pin "C") (pinfunction "C_C") (pintype "passive"))
      (node (ref "IC1") (pin "1") (pinfunction "OUT_1") (pintype "passive"))
      (node (ref "IC7") (pin "4") (pinfunction "V-_4") (pintype "power_in"))
      (node (ref "X3") (pin "7") (pinfunction "S_7") (pintype "passive"))
    )
    (net (code "119") (name "unconnected-(IC2-SD-Pad3)") (class "Default")
      (node (ref "IC2") (pin "3") (pinfunction "SD_3") (pintype "input"))
    )
    (net (code "120") (name "unconnected-(IC2-SENSE-Pad2)") (class "Default")
      (node (ref "IC2") (pin "2") (pinfunction "SENSE_2") (pintype "input"))
    )
    (net (code "121") (name "unconnected-(IC2-VTAP-Pad6)") (class "Default")
      (node (ref "IC2") (pin "6") (pinfunction "VTAP_6") (pintype "input"))
    )
  )
)
